# interface.net
KiCad netlist of a schematic drawn in Altium Designer
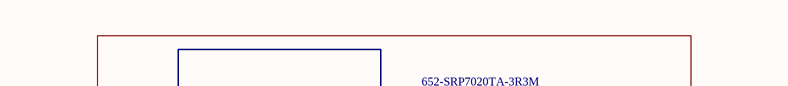
[diagram p0: interface.SchDoc, top left]
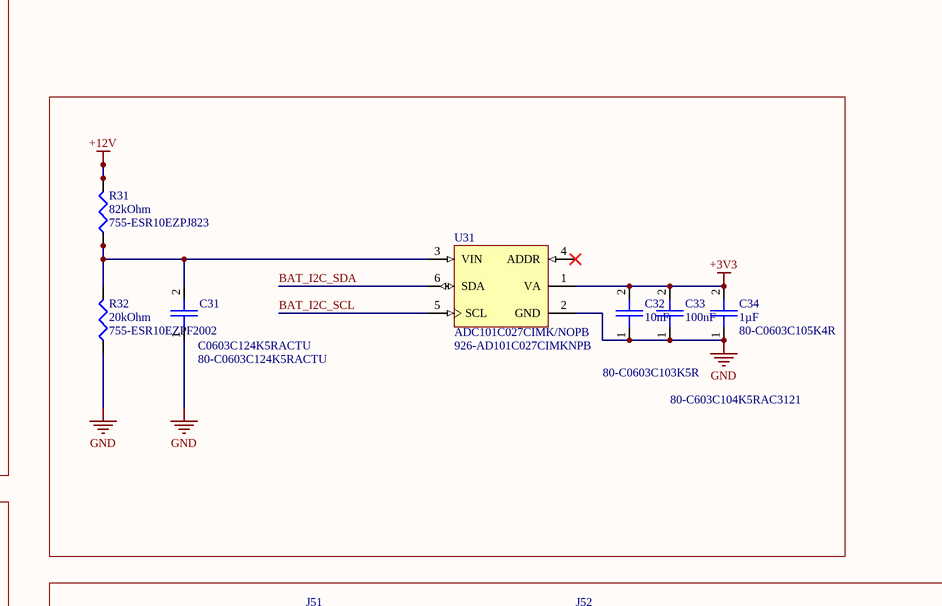
[diagram p1: interface.SchDoc, top right]
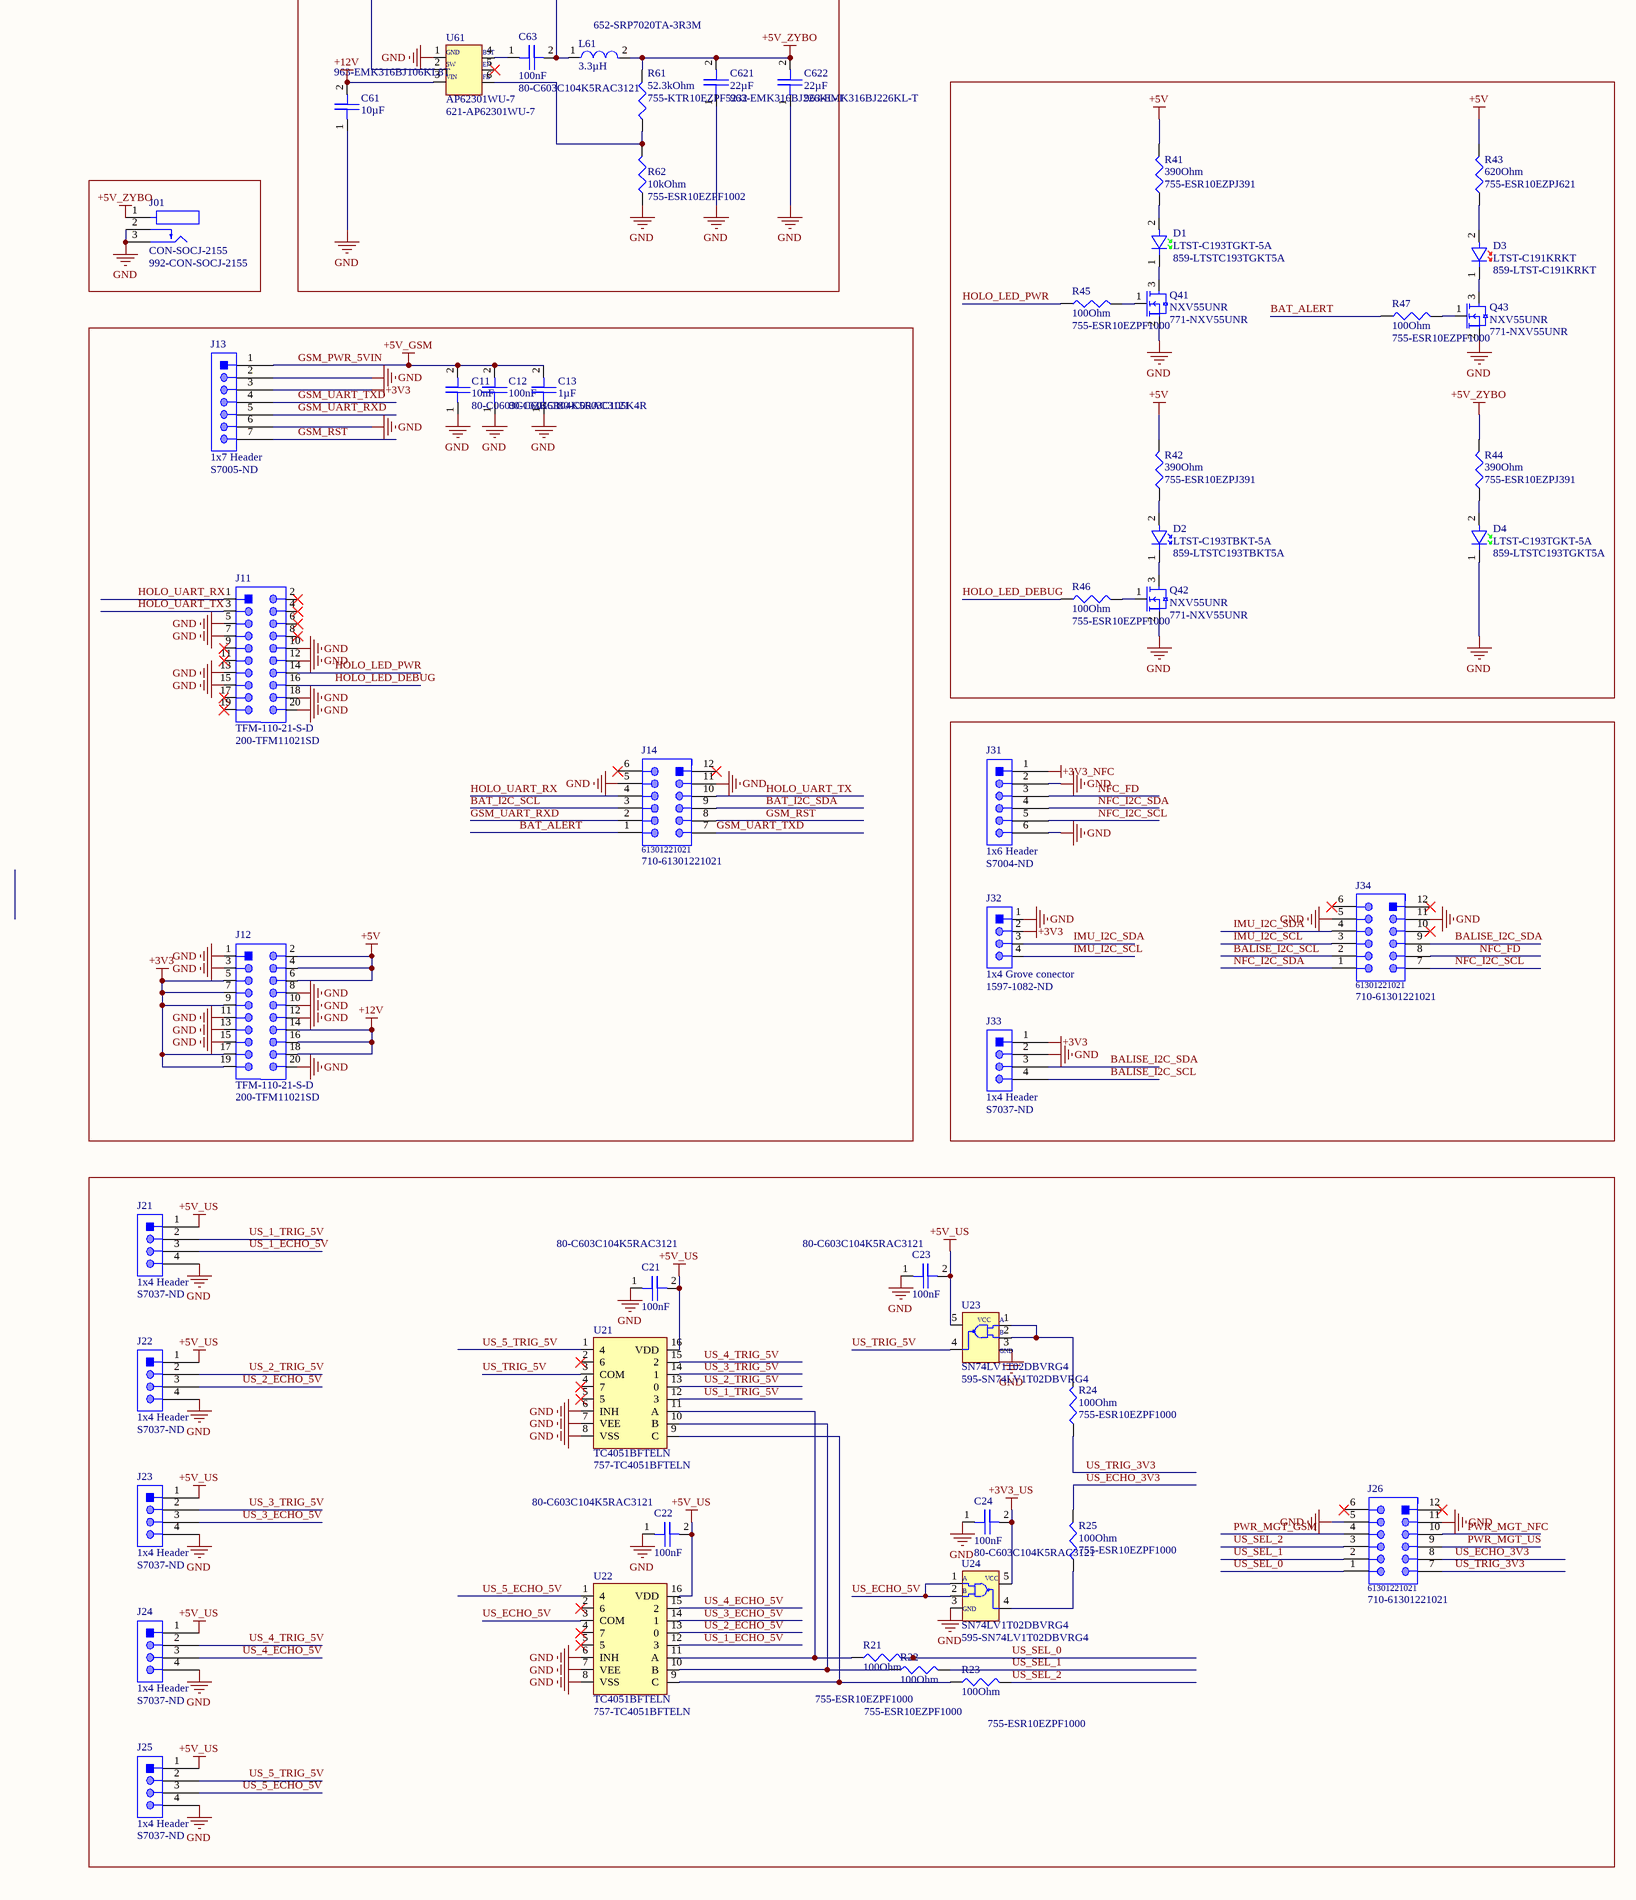
[diagram p2: interface.SchDoc, bottom left]
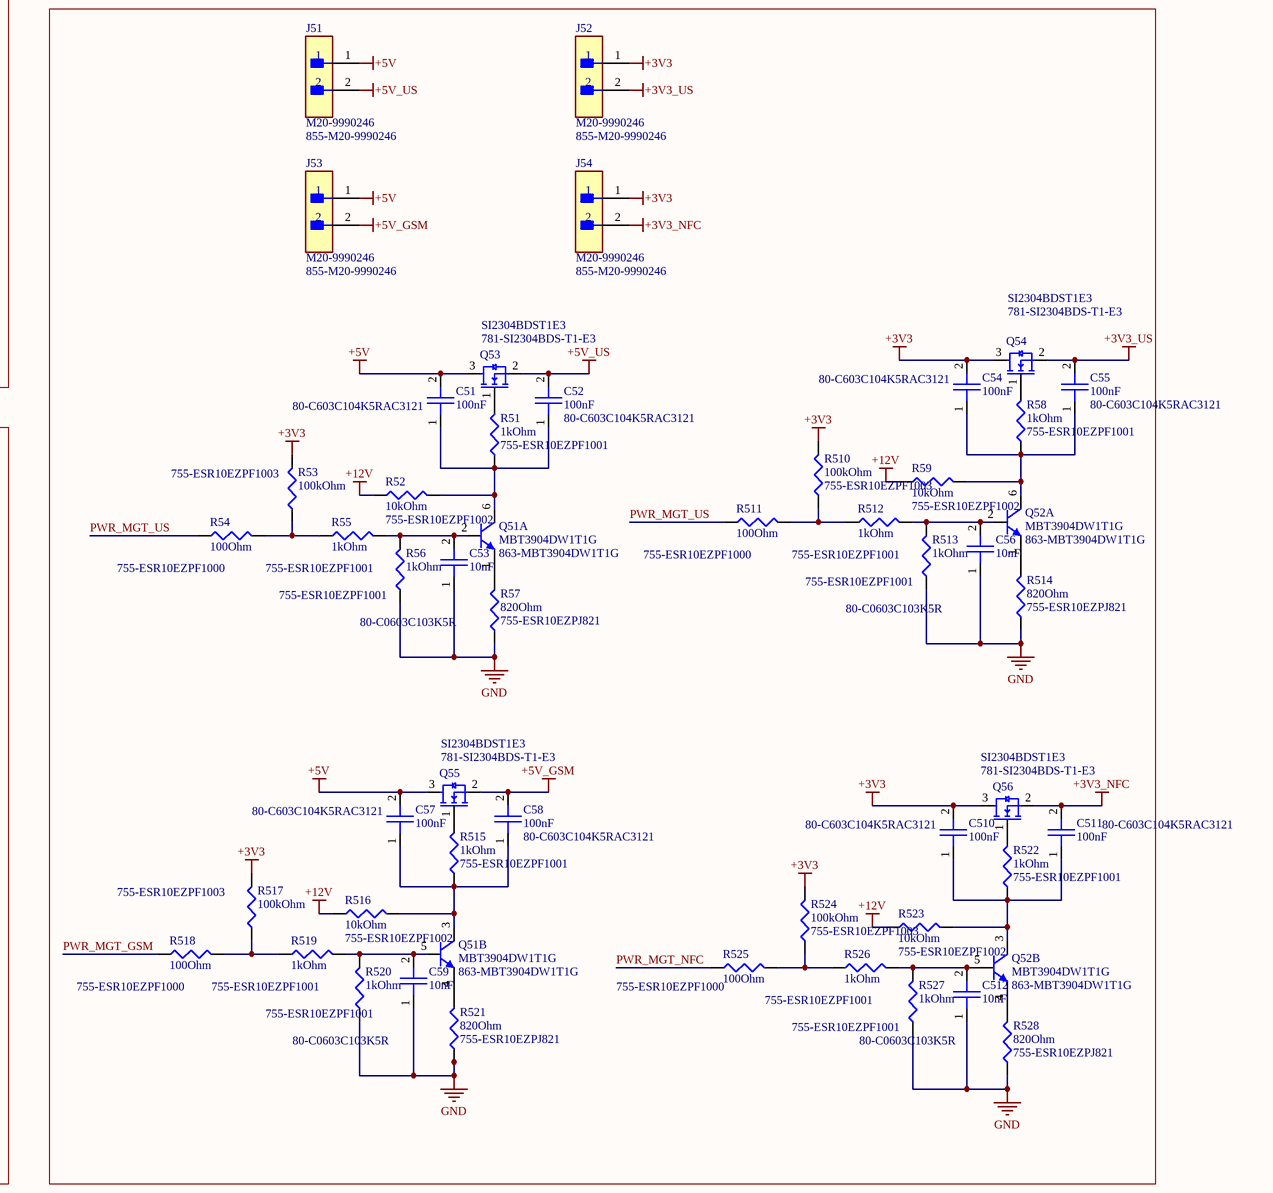
[diagram p3: interface.SchDoc, bottom right]

(export (version "E")
  (design (tool "Eeschema 10.0.6"))
  (components
    (comp (ref "C11")
      (value "10nF")
      (footprint "FP-C0603C-CF-IPC_A")
      (description "CAP CER 10000PF 50V X7R 0603")
      (fields
        (field (name "MANUFACTURER") "KEMET")
        (field (name "MANUFACTURER PART NUMBER") "C0603C103K5RACTU")
        (field (name "SUPPLIER PART NUMBER 1") "80-C0603C103K5R")
      )
      (libsource (lib "interface_Schlib") (part "C0603C103K5RACTU"))
    )
    (comp (ref "C12")
      (value "100nF")
      (footprint "FP-C0603C104K5RAC3121-IPC_A")
      (description "Cap Ceramic 0.1uF 50V X7R 10% Pad SMD 0603 125°C T/R")
      (fields
        (field (name "MANUFACTURER") "KEMET")
        (field (name "MANUFACTURER PART NUMBER") "C0603C104K5RAC3121")
        (field (name "SUPPLIER PART NUMBER 1") "80-C603C104K5RAC3121")
      )
      (libsource (lib "interface_Schlib") (part "C0603C104K5RAC3121"))
    )
    (comp (ref "C13")
      (value "1µF")
      (footprint "CAPC1608X90X35NL15T15")
      (description "Cap Ceramic 1uF 16V X7R 10% SMD 0603 125°C Paper T/R")
      (fields
        (field (name "MANUFACTURER") "KEMET")
        (field (name "MANUFACTURER PART NUMBER") "C0603C105K4RACTU")
        (field (name "SUPPLIER PART NUMBER 1") "80-C0603C105K4R")
      )
      (libsource (lib "interface_Schlib") (part "C0603C105K4RACTU"))
    )
    (comp (ref "C21")
      (value "100nF")
      (footprint "FP-C0603C104K5RAC3121-IPC_A")
      (description "Cap Ceramic 0.1uF 50V X7R 10% Pad SMD 0603 125°C T/R")
      (fields
        (field (name "MANUFACTURER") "KEMET")
        (field (name "MANUFACTURER PART NUMBER") "C0603C104K5RAC3121")
        (field (name "SUPPLIER PART NUMBER 1") "80-C603C104K5RAC3121")
      )
      (libsource (lib "interface_Schlib") (part "C0603C104K5RAC3121"))
    )
    (comp (ref "C22")
      (value "100nF")
      (footprint "FP-C0603C104K5RAC3121-IPC_A")
      (description "Cap Ceramic 0.1uF 50V X7R 10% Pad SMD 0603 125°C T/R")
      (fields
        (field (name "MANUFACTURER") "KEMET")
        (field (name "MANUFACTURER PART NUMBER") "C0603C104K5RAC3121")
        (field (name "SUPPLIER PART NUMBER 1") "80-C603C104K5RAC3121")
      )
      (libsource (lib "interface_Schlib") (part "C0603C104K5RAC3121"))
    )
    (comp (ref "C23")
      (value "100nF")
      (footprint "FP-C0603C104K5RAC3121-IPC_A")
      (description "Cap Ceramic 0.1uF 50V X7R 10% Pad SMD 0603 125°C T/R")
      (fields
        (field (name "MANUFACTURER") "KEMET")
        (field (name "MANUFACTURER PART NUMBER") "C0603C104K5RAC3121")
        (field (name "SUPPLIER PART NUMBER 1") "80-C603C104K5RAC3121")
      )
      (libsource (lib "interface_Schlib") (part "C0603C104K5RAC3121"))
    )
    (comp (ref "C24")
      (value "100nF")
      (footprint "FP-C0603C104K5RAC3121-IPC_A")
      (description "Cap Ceramic 0.1uF 50V X7R 10% Pad SMD 0603 125°C T/R")
      (fields
        (field (name "MANUFACTURER") "KEMET")
        (field (name "MANUFACTURER PART NUMBER") "C0603C104K5RAC3121")
        (field (name "SUPPLIER PART NUMBER 1") "80-C603C104K5RAC3121")
      )
      (libsource (lib "interface_Schlib") (part "C0603C104K5RAC3121"))
    )
    (comp (ref "C31")
      (value "C0603C124K5RACTU")
      (footprint "FP-C0603C-CF-IPC_A")
      (description "0603 C 120nF Ceramic Multilayer Capacitor; 50 V; +125degC; X7R Dielec; +/-10%")
      (fields
        (field (name "MANUFACTURER") "KEMET")
        (field (name "TOLERANCE") "10%")
        (field (name "SUPPLIER PART NUMBER 1") "80-C0603C124K5RACTU")
      )
      (libsource (lib "interface_Schlib") (part "C0603C124K5RACTU"))
    )
    (comp (ref "C32")
      (value "10nF")
      (footprint "FP-C0603C-CF-IPC_A")
      (description "CAP CER 10000PF 50V X7R 0603")
      (fields
        (field (name "MANUFACTURER") "KEMET")
        (field (name "MANUFACTURER PART NUMBER") "C0603C103K5RACTU")
        (field (name "SUPPLIER PART NUMBER 1") "80-C0603C103K5R")
      )
      (libsource (lib "interface_Schlib") (part "C0603C103K5RACTU"))
    )
    (comp (ref "C33")
      (value "100nF")
      (footprint "FP-C0603C104K5RAC3121-IPC_A")
      (description "Cap Ceramic 0.1uF 50V X7R 10% Pad SMD 0603 125°C T/R")
      (fields
        (field (name "MANUFACTURER") "KEMET")
        (field (name "MANUFACTURER PART NUMBER") "C0603C104K5RAC3121")
        (field (name "SUPPLIER PART NUMBER 1") "80-C603C104K5RAC3121")
      )
      (libsource (lib "interface_Schlib") (part "C0603C104K5RAC3121"))
    )
    (comp (ref "C34")
      (value "1µF")
      (footprint "CAPC1608X90X35NL15T15")
      (description "Cap Ceramic 1uF 16V X7R 10% SMD 0603 125°C Paper T/R")
      (fields
        (field (name "MANUFACTURER") "KEMET")
        (field (name "MANUFACTURER PART NUMBER") "C0603C105K4RACTU")
        (field (name "SUPPLIER PART NUMBER 1") "80-C0603C105K4R")
      )
      (libsource (lib "interface_Schlib") (part "C0603C105K4RACTU"))
    )
    (comp (ref "C51")
      (value "100nF")
      (footprint "FP-C0603C104K5RAC3121-IPC_A")
      (description "Cap Ceramic 0.1uF 50V X7R 10% Pad SMD 0603 125°C T/R")
      (fields
        (field (name "MANUFACTURER") "KEMET")
        (field (name "MANUFACTURER PART NUMBER") "C0603C104K5RAC3121")
        (field (name "SUPPLIER PART NUMBER 1") "80-C603C104K5RAC3121")
      )
      (libsource (lib "interface_Schlib") (part "C0603C104K5RAC3121"))
    )
    (comp (ref "C52")
      (value "100nF")
      (footprint "FP-C0603C104K5RAC3121-IPC_A")
      (description "Cap Ceramic 0.1uF 50V X7R 10% Pad SMD 0603 125°C T/R")
      (fields
        (field (name "MANUFACTURER") "KEMET")
        (field (name "MANUFACTURER PART NUMBER") "C0603C104K5RAC3121")
        (field (name "SUPPLIER PART NUMBER 1") "80-C603C104K5RAC3121")
      )
      (libsource (lib "interface_Schlib") (part "C0603C104K5RAC3121"))
    )
    (comp (ref "C53")
      (value "10nF")
      (footprint "FP-C0603C-CF-IPC_A")
      (description "CAP CER 10000PF 50V X7R 0603")
      (fields
        (field (name "MANUFACTURER") "KEMET")
        (field (name "MANUFACTURER PART NUMBER") "C0603C103K5RACTU")
        (field (name "SUPPLIER PART NUMBER 1") "80-C0603C103K5R")
      )
      (libsource (lib "interface_Schlib") (part "C0603C103K5RACTU"))
    )
    (comp (ref "C54")
      (value "100nF")
      (footprint "FP-C0603C104K5RAC3121-IPC_A")
      (description "Cap Ceramic 0.1uF 50V X7R 10% Pad SMD 0603 125°C T/R")
      (fields
        (field (name "MANUFACTURER") "KEMET")
        (field (name "MANUFACTURER PART NUMBER") "C0603C104K5RAC3121")
        (field (name "SUPPLIER PART NUMBER 1") "80-C603C104K5RAC3121")
      )
      (libsource (lib "interface_Schlib") (part "C0603C104K5RAC3121"))
    )
    (comp (ref "C55")
      (value "100nF")
      (footprint "FP-C0603C104K5RAC3121-IPC_A")
      (description "Cap Ceramic 0.1uF 50V X7R 10% Pad SMD 0603 125°C T/R")
      (fields
        (field (name "MANUFACTURER") "KEMET")
        (field (name "MANUFACTURER PART NUMBER") "C0603C104K5RAC3121")
        (field (name "SUPPLIER PART NUMBER 1") "80-C603C104K5RAC3121")
      )
      (libsource (lib "interface_Schlib") (part "C0603C104K5RAC3121"))
    )
    (comp (ref "C56")
      (value "10nF")
      (footprint "FP-C0603C-CF-IPC_A")
      (description "CAP CER 10000PF 50V X7R 0603")
      (fields
        (field (name "MANUFACTURER") "KEMET")
        (field (name "MANUFACTURER PART NUMBER") "C0603C103K5RACTU")
        (field (name "SUPPLIER PART NUMBER 1") "80-C0603C103K5R")
      )
      (libsource (lib "interface_Schlib") (part "C0603C103K5RACTU"))
    )
    (comp (ref "C57")
      (value "100nF")
      (footprint "FP-C0603C104K5RAC3121-IPC_A")
      (description "Cap Ceramic 0.1uF 50V X7R 10% Pad SMD 0603 125°C T/R")
      (fields
        (field (name "MANUFACTURER") "KEMET")
        (field (name "MANUFACTURER PART NUMBER") "C0603C104K5RAC3121")
        (field (name "SUPPLIER PART NUMBER 1") "80-C603C104K5RAC3121")
      )
      (libsource (lib "interface_Schlib") (part "C0603C104K5RAC3121"))
    )
    (comp (ref "C58")
      (value "100nF")
      (footprint "FP-C0603C104K5RAC3121-IPC_A")
      (description "Cap Ceramic 0.1uF 50V X7R 10% Pad SMD 0603 125°C T/R")
      (fields
        (field (name "MANUFACTURER") "KEMET")
        (field (name "MANUFACTURER PART NUMBER") "C0603C104K5RAC3121")
        (field (name "SUPPLIER PART NUMBER 1") "80-C603C104K5RAC3121")
      )
      (libsource (lib "interface_Schlib") (part "C0603C104K5RAC3121"))
    )
    (comp (ref "C59")
      (value "10nF")
      (footprint "FP-C0603C-CF-IPC_A")
      (description "CAP CER 10000PF 50V X7R 0603")
      (fields
        (field (name "MANUFACTURER") "KEMET")
        (field (name "MANUFACTURER PART NUMBER") "C0603C103K5RACTU")
        (field (name "SUPPLIER PART NUMBER 1") "80-C0603C103K5R")
      )
      (libsource (lib "interface_Schlib") (part "C0603C103K5RACTU"))
    )
    (comp (ref "C61")
      (value "10µF")
      (footprint "FP-1206-L_3_2_0_15-W_1_6-IPC_A")
      (description "Capacitor Ceramic 10uF 16V X5R 10% SMD 1206 85°C Embossed T/R")
      (fields
        (field (name "MANUFACTURER") "Taiyo Yuden")
        (field (name "MANUFACTURER PART NUMBER") "EMK316BJ106KL8T")
        (field (name "SUPPLIER PART NUMBER 1") "963-EMK316BJ106KL8T")
      )
      (libsource (lib "interface_Schlib") (part "EMK316BJ106KL8T"))
    )
    (comp (ref "C63")
      (value "100nF")
      (footprint "FP-C0603C104K5RAC3121-IPC_A")
      (description "Cap Ceramic 0.1uF 50V X7R 10% Pad SMD 0603 125°C T/R")
      (fields
        (field (name "MANUFACTURER") "KEMET")
        (field (name "MANUFACTURER PART NUMBER") "C0603C104K5RAC3121")
        (field (name "SUPPLIER PART NUMBER 1") "80-C603C104K5RAC3121")
      )
      (libsource (lib "interface_Schlib") (part "C0603C104K5RAC3121"))
    )
    (comp (ref "C510")
      (value "100nF")
      (footprint "FP-C0603C104K5RAC3121-IPC_A")
      (description "Cap Ceramic 0.1uF 50V X7R 10% Pad SMD 0603 125°C T/R")
      (fields
        (field (name "MANUFACTURER") "KEMET")
        (field (name "MANUFACTURER PART NUMBER") "C0603C104K5RAC3121")
        (field (name "SUPPLIER PART NUMBER 1") "80-C603C104K5RAC3121")
      )
      (libsource (lib "interface_Schlib") (part "C0603C104K5RAC3121"))
    )
    (comp (ref "C511")
      (value "100nF")
      (footprint "FP-C0603C104K5RAC3121-IPC_A")
      (description "Cap Ceramic 0.1uF 50V X7R 10% Pad SMD 0603 125°C T/R")
      (fields
        (field (name "MANUFACTURER") "KEMET")
        (field (name "MANUFACTURER PART NUMBER") "C0603C104K5RAC3121")
        (field (name "SUPPLIER PART NUMBER 1") "80-C603C104K5RAC3121")
      )
      (libsource (lib "interface_Schlib") (part "C0603C104K5RAC3121"))
    )
    (comp (ref "C512")
      (value "10nF")
      (footprint "FP-C0603C-CF-IPC_A")
      (description "CAP CER 10000PF 50V X7R 0603")
      (fields
        (field (name "MANUFACTURER") "KEMET")
        (field (name "MANUFACTURER PART NUMBER") "C0603C103K5RACTU")
        (field (name "SUPPLIER PART NUMBER 1") "80-C0603C103K5R")
      )
      (libsource (lib "interface_Schlib") (part "C0603C103K5RACTU"))
    )
    (comp (ref "C621")
      (value "22µF")
      (footprint "CAPC3216X180N")
      (description "Cap Ceramic 22uF 16V X7R 10% SMD 0805 125°C Paper T/R")
      (fields
        (field (name "MANUFACTURER") "Taiyo Yuden")
        (field (name "MANUFACTURER PART NUMBER") "EMK316BJ226KL-T")
        (field (name "SUPPLIER PART NUMBER 1") "963-EMK316BJ226KL-T")
      )
      (libsource (lib "station_de_charge_SchLib") (part "EMK316BJ226KL-T"))
    )
    (comp (ref "C622")
      (value "22µF")
      (footprint "CAPC3216X180N")
      (description "Cap Ceramic 22uF 16V X7R 10% SMD 0805 125°C Paper T/R")
      (fields
        (field (name "MANUFACTURER") "Taiyo Yuden")
        (field (name "MANUFACTURER PART NUMBER") "EMK316BJ226KL-T")
        (field (name "SUPPLIER PART NUMBER 1") "963-EMK316BJ226KL-T")
      )
      (libsource (lib "station_de_charge_SchLib") (part "EMK316BJ226KL-T"))
    )
    (comp (ref "D1")
      (value "LTST-C193TGKT-5A")
      (footprint "FP-LTST-C193TGKT-5A")
      (description "0603(H=0.35mm) 绿色 λD=520nm~535nm VR=5V VF=2.5V~3.1V IF=5mA PD=76mW")
      (fields
        (field (name "MANUFACTURER") "Vishay Lite-On")
        (field (name "SUPPLIER PART NUMBER 1") "859-LTSTC193TGKT5A")
      )
      (libsource (lib "interface_Schlib") (part "LTST-C193TGKT-5A"))
    )
    (comp (ref "D2")
      (value "LTST-C193TBKT-5A")
      (footprint "FP-LTST-C193TBKT-5A-MFG")
      (description "0603(H=0.35mm) 蓝色 λD=465nm~475nm VR=5V VF=2.65V~3.05V IF=5mA PD=76mW")
      (fields
        (field (name "MANUFACTURER") "Vishay Lite-On")
        (field (name "SUPPLIER PART NUMBER 1") "859-LTSTC193TBKT5A")
      )
      (libsource (lib "interface_Schlib") (part "LTST-C193TBKT-5A"))
    )
    (comp (ref "D3")
      (value "LTST-C191KRKT")
      (footprint "FP-LTST-C191KRKT")
      (description "0603(H=0.65mm) 红色 λD=631nm VR=5V VF=2.0V~2.4V IF=20mA PD=75mW")
      (fields
        (field (name "MANUFACTURER") "Vishay Lite-On")
        (field (name "SUPPLIER PART NUMBER 1") "859-LTST-C191KRKT")
        (field (name "VOLTAGE") "2V")
      )
      (libsource (lib "interface_Schlib") (part "LTST-C191KRKT"))
    )
    (comp (ref "D4")
      (value "LTST-C193TGKT-5A")
      (footprint "FP-LTST-C193TGKT-5A")
      (description "0603(H=0.35mm) 绿色 λD=520nm~535nm VR=5V VF=2.5V~3.1V IF=5mA PD=76mW")
      (fields
        (field (name "MANUFACTURER") "Vishay Lite-On")
        (field (name "SUPPLIER PART NUMBER 1") "859-LTSTC193TGKT5A")
      )
      (libsource (lib "interface_Schlib") (part "LTST-C193TGKT-5A"))
    )
    (comp (ref "J01")
      (value "CON-SOCJ-2155")
      (footprint "GRAVITECH_CON-SOCJ-2155")
      (description "DC Power Connectors Power Jack/Connector 2.1mm x 5.5mm")
      (fields
        (field (name "MANUFACTURER") "Gravitech")
        (field (name "SUPPLIER PART NUMBER 1") "992-CON-SOCJ-2155")
      )
      (libsource (lib "interface_Schlib") (part "CON-SOCJ-2155"))
    )
    (comp (ref "J11")
      (value "TFM-110-21-S-D")
      (footprint "SAMTEC_TFM-110-21-S-D")
      (fields (field (name "MANUFACTURER") "Samtec") (field (name "SUPPLIER PART NUMBER 1") "200-TFM11021SD"))
      (libsource (lib "interface_Schlib") (part "TFM-110-21-S-D"))
    )
    (comp (ref "J12")
      (value "TFM-110-21-S-D")
      (footprint "SAMTEC_TFM-110-21-S-D")
      (fields (field (name "MANUFACTURER") "Samtec") (field (name "SUPPLIER PART NUMBER 1") "200-TFM11021SD"))
      (libsource (lib "interface_Schlib") (part "TFM-110-21-S-D"))
    )
    (comp (ref "J13")
      (value "1x7 Header")
      (footprint "header 1x7")
      (description "Female, 7C, Straight, .100\"CC; 3.20mm Tail, No Mt. 100u\" Tin; PBT, Phos Bronze, 105 C")
      (fields
        (field (name "MANUFACTURER") "Sullins")
        (field (name "MANUFACTURER PART NUMBER") "PPTC071LFBN-RC")
        (field (name "SUPPLIER PART NUMBER 1") "S7005-ND")
      )
      (libsource (lib "interface_Schlib") (part "PPTC071LFBN-RC"))
    )
    (comp (ref "J14")
      (value "61301221021")
      (footprint "61301221021")
      (description "THT Angled Pin Header WR-PHD, Pitch 2.54 mm, Dual Row, 12 pins")
      (fields
        (field (name "MANUFACTURER") "Wurth Elektronik")
        (field (name "SUPPLIER PART NUMBER 1") "710-61301221021")
        (field (name "PUBLISHER") "WurthElektronik")
      )
      (libsource (lib "interface_Schlib") (part "61301221021"))
    )
    (comp (ref "J21")
      (value "1x4 Header")
      (footprint "header 1x4")
      (description "4 Positions Embase Connecteur 0,100 po (2,54mm) Trou traversant Or")
      (fields
        (field (name "MANUFACTURER") "Sullins")
        (field (name "MANUFACTURER PART NUMBER") "PPPC041LFBN-RC")
        (field (name "SUPPLIER PART NUMBER 1") "S7037-ND")
      )
      (libsource (lib "interface_Schlib") (part "PPPC041LFBN-RC"))
    )
    (comp (ref "J22")
      (value "1x4 Header")
      (footprint "header 1x4")
      (description "4 Positions Embase Connecteur 0,100 po (2,54mm) Trou traversant Or")
      (fields
        (field (name "MANUFACTURER") "Sullins")
        (field (name "MANUFACTURER PART NUMBER") "PPPC041LFBN-RC")
        (field (name "SUPPLIER PART NUMBER 1") "S7037-ND")
      )
      (libsource (lib "interface_Schlib") (part "PPPC041LFBN-RC"))
    )
    (comp (ref "J23")
      (value "1x4 Header")
      (footprint "header 1x4")
      (description "4 Positions Embase Connecteur 0,100 po (2,54mm) Trou traversant Or")
      (fields
        (field (name "MANUFACTURER") "Sullins")
        (field (name "MANUFACTURER PART NUMBER") "PPPC041LFBN-RC")
        (field (name "SUPPLIER PART NUMBER 1") "S7037-ND")
      )
      (libsource (lib "interface_Schlib") (part "PPPC041LFBN-RC"))
    )
    (comp (ref "J24")
      (value "1x4 Header")
      (footprint "header 1x4")
      (description "4 Positions Embase Connecteur 0,100 po (2,54mm) Trou traversant Or")
      (fields
        (field (name "MANUFACTURER") "Sullins")
        (field (name "MANUFACTURER PART NUMBER") "PPPC041LFBN-RC")
        (field (name "SUPPLIER PART NUMBER 1") "S7037-ND")
      )
      (libsource (lib "interface_Schlib") (part "PPPC041LFBN-RC"))
    )
    (comp (ref "J25")
      (value "1x4 Header")
      (footprint "header 1x4")
      (description "4 Positions Embase Connecteur 0,100 po (2,54mm) Trou traversant Or")
      (fields
        (field (name "MANUFACTURER") "Sullins")
        (field (name "MANUFACTURER PART NUMBER") "PPPC041LFBN-RC")
        (field (name "SUPPLIER PART NUMBER 1") "S7037-ND")
      )
      (libsource (lib "interface_Schlib") (part "PPPC041LFBN-RC"))
    )
    (comp (ref "J26")
      (value "61301221021")
      (footprint "61301221021")
      (description "THT Angled Pin Header WR-PHD, Pitch 2.54 mm, Dual Row, 12 pins")
      (fields
        (field (name "MANUFACTURER") "Wurth Elektronik")
        (field (name "SUPPLIER PART NUMBER 1") "710-61301221021")
        (field (name "PUBLISHER") "WurthElektronik")
      )
      (libsource (lib "interface_Schlib") (part "61301221021"))
    )
    (comp (ref "J31")
      (value "1x6 Header")
      (footprint "header 1x6")
      (description "Female, 6 C, Straight, .100\"CC; 3.20mm Tail, No Mt. 100u\" Tin; PBT, Phos Bronze, 105 C")
      (fields
        (field (name "MANUFACTURER") "Sullins")
        (field (name "MANUFACTURER PART NUMBER") "PPTC061LFBN-RC")
        (field (name "SUPPLIER PART NUMBER 1") "S7004-ND")
      )
      (libsource (lib "interface_Schlib") (part "PPTC061LFBN-RC"))
    )
    (comp (ref "J32")
      (value "1x4 Grove conector")
      (footprint "FP-110990030")
      (description "Grove - Universal 4 pin connector [Seeed Studio] 110990030 Grove - Universal 4 pin connector")
      (fields
        (field (name "MANUFACTURER") "Seeed Studio")
        (field (name "MANUFACTURER PART NUMBER") "110990030")
        (field (name "SUPPLIER PART NUMBER 1") "1597-1082-ND")
      )
      (libsource (lib "interface_Schlib") (part "110990030"))
    )
    (comp (ref "J33")
      (value "1x4 Header")
      (footprint "header 1x4")
      (description "4 Positions Embase Connecteur 0,100 po (2,54mm) Trou traversant Or")
      (fields
        (field (name "MANUFACTURER") "Sullins")
        (field (name "MANUFACTURER PART NUMBER") "PPPC041LFBN-RC")
        (field (name "SUPPLIER PART NUMBER 1") "S7037-ND")
      )
      (libsource (lib "interface_Schlib") (part "PPPC041LFBN-RC"))
    )
    (comp (ref "J34")
      (value "61301221021")
      (footprint "61301221021")
      (description "THT Angled Pin Header WR-PHD, Pitch 2.54 mm, Dual Row, 12 pins")
      (fields
        (field (name "MANUFACTURER") "Wurth Elektronik")
        (field (name "SUPPLIER PART NUMBER 1") "710-61301221021")
        (field (name "PUBLISHER") "WurthElektronik")
      )
      (libsource (lib "interface_Schlib") (part "61301221021"))
    )
    (comp (ref "J51")
      (value "M20-9990246")
      (footprint "FP-M20-9990246-MFG")
      (description "2.54mm (0.1\") Pitch SIL Vertical PC Tail Pin Header, 6.1mm mating pin height, tin, 2 contacts")
      (fields
        (field (name "MANUFACTURER") "Harwin")
        (field (name "SUPPLIER PART NUMBER 1") "855-M20-9990246")
      )
      (libsource (lib "interface_Schlib") (part "M20-9990246"))
    )
    (comp (ref "J52")
      (value "M20-9990246")
      (footprint "FP-M20-9990246-MFG")
      (description "2.54mm (0.1\") Pitch SIL Vertical PC Tail Pin Header, 6.1mm mating pin height, tin, 2 contacts")
      (fields
        (field (name "MANUFACTURER") "Harwin")
        (field (name "SUPPLIER PART NUMBER 1") "855-M20-9990246")
      )
      (libsource (lib "interface_Schlib") (part "M20-9990246"))
    )
    (comp (ref "J53")
      (value "M20-9990246")
      (footprint "FP-M20-9990246-MFG")
      (description "2.54mm (0.1\") Pitch SIL Vertical PC Tail Pin Header, 6.1mm mating pin height, tin, 2 contacts")
      (fields
        (field (name "MANUFACTURER") "Harwin")
        (field (name "SUPPLIER PART NUMBER 1") "855-M20-9990246")
      )
      (libsource (lib "interface_Schlib") (part "M20-9990246"))
    )
    (comp (ref "J54")
      (value "M20-9990246")
      (footprint "FP-M20-9990246-MFG")
      (description "2.54mm (0.1\") Pitch SIL Vertical PC Tail Pin Header, 6.1mm mating pin height, tin, 2 contacts")
      (fields
        (field (name "MANUFACTURER") "Harwin")
        (field (name "SUPPLIER PART NUMBER 1") "855-M20-9990246")
      )
      (libsource (lib "interface_Schlib") (part "M20-9990246"))
    )
    (comp (ref "L61")
      (value "3.3µH")
      (footprint "INDC7066X20N")
      (fields
        (field (name "MANUFACTURER") "Bourns")
        (field (name "MANUFACTURER PART NUMBER") "SRP7020TA-3R3M")
        (field (name "SUPPLIER PART NUMBER 1") "652-SRP7020TA-3R3M")
      )
      (libsource (lib "interface_Schlib") (part "SRP7020TA-3R3M"))
    )
    (comp (ref "Q41")
      (value "NXV55UNR")
      (footprint "SOT95P230X110-3N")
      (description "Transistor MOSFET N-Channel 30V 2.3A 3-Pin SOT-23")
      (fields (field (name "MANUFACTURER") "Nexperia") (field (name "SUPPLIER PART NUMBER 1") "771-NXV55UNR"))
      (libsource (lib "interface_Schlib") (part "NXV55UNR"))
    )
    (comp (ref "Q42")
      (value "NXV55UNR")
      (footprint "SOT95P230X110-3N")
      (description "Transistor MOSFET N-Channel 30V 2.3A 3-Pin SOT-23")
      (fields (field (name "MANUFACTURER") "Nexperia") (field (name "SUPPLIER PART NUMBER 1") "771-NXV55UNR"))
      (libsource (lib "interface_Schlib") (part "NXV55UNR"))
    )
    (comp (ref "Q43")
      (value "NXV55UNR")
      (footprint "SOT95P230X110-3N")
      (description "Transistor MOSFET N-Channel 30V 2.3A 3-Pin SOT-23")
      (fields (field (name "MANUFACTURER") "Nexperia") (field (name "SUPPLIER PART NUMBER 1") "771-NXV55UNR"))
      (libsource (lib "interface_Schlib") (part "NXV55UNR"))
    )
    (comp (ref "Q51")
      (value "MBT3904DW1T1G")
      (footprint "ONSC-SOT-363-6-419B-02_W_V")
      (description "Dual General Purpose Transistors, 6-Pin SOT-363, Pb-Free, Tape and Reel")
      (fields
        (field (name "MANUFACTURER") "On Semiconductor")
        (field (name "SUPPLIER PART NUMBER 1") "863-MBT3904DW1T1G")
      )
      (libsource (lib "interface_Schlib") (part "CMP-1048-00877-1"))
    )
    (comp (ref "Q52")
      (value "MBT3904DW1T1G")
      (footprint "ONSC-SOT-363-6-419B-02_W_V")
      (description "Dual General Purpose Transistors, 6-Pin SOT-363, Pb-Free, Tape and Reel")
      (fields
        (field (name "MANUFACTURER") "On Semiconductor")
        (field (name "SUPPLIER PART NUMBER 1") "863-MBT3904DW1T1G")
      )
      (libsource (lib "interface_Schlib") (part "CMP-1048-00877-1"))
    )
    (comp (ref "Q53")
      (value "SI2304BDST1E3")
      (footprint "FP-SI2304BDST1E3")
      (description "Single N-Channel 30 V 0.07 Ohms Surface Mount Power Mosfet - SOT-23")
      (fields
        (field (name "MANUFACTURER") "Vishay")
        (field (name "SUPPLIER PART NUMBER 1") "781-SI2304BDS-T1-E3")
      )
      (libsource (lib "interface_Schlib") (part "SI2304BDST1E3"))
    )
    (comp (ref "Q54")
      (value "SI2304BDST1E3")
      (footprint "FP-SI2304BDST1E3")
      (description "Single N-Channel 30 V 0.07 Ohms Surface Mount Power Mosfet - SOT-23")
      (fields
        (field (name "MANUFACTURER") "Vishay")
        (field (name "SUPPLIER PART NUMBER 1") "781-SI2304BDS-T1-E3")
      )
      (libsource (lib "interface_Schlib") (part "SI2304BDST1E3"))
    )
    (comp (ref "Q55")
      (value "SI2304BDST1E3")
      (footprint "FP-SI2304BDST1E3")
      (description "Single N-Channel 30 V 0.07 Ohms Surface Mount Power Mosfet - SOT-23")
      (fields
        (field (name "MANUFACTURER") "Vishay")
        (field (name "SUPPLIER PART NUMBER 1") "781-SI2304BDS-T1-E3")
      )
      (libsource (lib "interface_Schlib") (part "SI2304BDST1E3"))
    )
    (comp (ref "Q56")
      (value "SI2304BDST1E3")
      (footprint "FP-SI2304BDST1E3")
      (description "Single N-Channel 30 V 0.07 Ohms Surface Mount Power Mosfet - SOT-23")
      (fields
        (field (name "MANUFACTURER") "Vishay")
        (field (name "SUPPLIER PART NUMBER 1") "781-SI2304BDS-T1-E3")
      )
      (libsource (lib "interface_Schlib") (part "SI2304BDST1E3"))
    )
    (comp (ref "R21")
      (value "100Ohm")
      (footprint "FP-ESR10-IPC_A")
      (description "Res Thick Film 0805 100 Ohm 1% 2/5W ±100ppm/°C Molded SMD Paper T/R")
      (fields
        (field (name "MANUFACTURER") "Rohm")
        (field (name "MANUFACTURER PART NUMBER") "ESR10EZPF1000")
        (field (name "SUPPLIER PART NUMBER 1") "755-ESR10EZPF1000")
      )
      (libsource (lib "interface_Schlib") (part "ESR10EZPF1000"))
    )
    (comp (ref "R22")
      (value "100Ohm")
      (footprint "FP-ESR10-IPC_A")
      (description "Res Thick Film 0805 100 Ohm 1% 2/5W ±100ppm/°C Molded SMD Paper T/R")
      (fields
        (field (name "MANUFACTURER") "Rohm")
        (field (name "MANUFACTURER PART NUMBER") "ESR10EZPF1000")
        (field (name "SUPPLIER PART NUMBER 1") "755-ESR10EZPF1000")
      )
      (libsource (lib "interface_Schlib") (part "ESR10EZPF1000"))
    )
    (comp (ref "R23")
      (value "100Ohm")
      (footprint "FP-ESR10-IPC_A")
      (description "Res Thick Film 0805 100 Ohm 1% 2/5W ±100ppm/°C Molded SMD Paper T/R")
      (fields
        (field (name "MANUFACTURER") "Rohm")
        (field (name "MANUFACTURER PART NUMBER") "ESR10EZPF1000")
        (field (name "SUPPLIER PART NUMBER 1") "755-ESR10EZPF1000")
      )
      (libsource (lib "interface_Schlib") (part "ESR10EZPF1000"))
    )
    (comp (ref "R24")
      (value "100Ohm")
      (footprint "FP-ESR10-IPC_A")
      (description "Res Thick Film 0805 100 Ohm 1% 2/5W ±100ppm/°C Molded SMD Paper T/R")
      (fields
        (field (name "MANUFACTURER") "Rohm")
        (field (name "MANUFACTURER PART NUMBER") "ESR10EZPF1000")
        (field (name "SUPPLIER PART NUMBER 1") "755-ESR10EZPF1000")
      )
      (libsource (lib "interface_Schlib") (part "ESR10EZPF1000"))
    )
    (comp (ref "R25")
      (value "100Ohm")
      (footprint "FP-ESR10-IPC_A")
      (description "Res Thick Film 0805 100 Ohm 1% 2/5W ±100ppm/°C Molded SMD Paper T/R")
      (fields
        (field (name "MANUFACTURER") "Rohm")
        (field (name "MANUFACTURER PART NUMBER") "ESR10EZPF1000")
        (field (name "SUPPLIER PART NUMBER 1") "755-ESR10EZPF1000")
      )
      (libsource (lib "interface_Schlib") (part "ESR10EZPF1000"))
    )
    (comp (ref "R31")
      (value "82kOhm")
      (footprint "FP-ESR10-IPC_A")
      (description "Res Anti-surge 0805 82K Ohm 0.4W 5% SMD")
      (fields
        (field (name "MANUFACTURER") "Rohm")
        (field (name "MANUFACTURER PART NUMBER") "ESR10EZPJ823")
        (field (name "SUPPLIER PART NUMBER 1") "755-ESR10EZPJ823")
      )
      (libsource (lib "interface_Schlib") (part "ESR10EZPJ823"))
    )
    (comp (ref "R32")
      (value "20kOhm")
      (footprint "FP-ESR10-IPC_A")
      (description "Res Thick Film 0805 20KOhm 1% 2/5W ±100ppm/°C Molded SMD Paper T/R")
      (fields
        (field (name "MANUFACTURER") "Rohm")
        (field (name "MANUFACTURER PART NUMBER") "ESR10EZPF2002")
        (field (name "SUPPLIER PART NUMBER 1") "755-ESR10EZPF2002")
      )
      (libsource (lib "interface_Schlib") (part "ESR10EZPF2002"))
    )
    (comp (ref "R41")
      (value "390Ohm")
      (footprint "FP-ESR10-IPC_A")
      (description "Res Thick Film 0805 390 Ohm 5% 0.4W ±200ppm/C Pad SMD Automotive T/R")
      (fields
        (field (name "MANUFACTURER") "Rohm")
        (field (name "MANUFACTURER PART NUMBER") "ESR10EZPJ391")
        (field (name "SUPPLIER PART NUMBER 1") "755-ESR10EZPJ391")
      )
      (libsource (lib "interface_Schlib") (part "ESR10EZPJ391"))
    )
    (comp (ref "R42")
      (value "390Ohm")
      (footprint "FP-ESR10-IPC_A")
      (description "Res Thick Film 0805 390 Ohm 5% 0.4W ±200ppm/C Pad SMD Automotive T/R")
      (fields
        (field (name "MANUFACTURER") "Rohm")
        (field (name "MANUFACTURER PART NUMBER") "ESR10EZPJ391")
        (field (name "SUPPLIER PART NUMBER 1") "755-ESR10EZPJ391")
      )
      (libsource (lib "interface_Schlib") (part "ESR10EZPJ391"))
    )
    (comp (ref "R43")
      (value "620Ohm")
      (footprint "FP-ESR10-IPC_A")
      (description "Res Thick Film 0805 620 Ohm 5% 0.4W ±200ppm/C Pad SMD Automotive T/R")
      (fields
        (field (name "MANUFACTURER") "Rohm")
        (field (name "MANUFACTURER PART NUMBER") "ESR10EZPJ621")
        (field (name "SUPPLIER PART NUMBER 1") "755-ESR10EZPJ621")
      )
      (libsource (lib "interface_Schlib") (part "ESR10EZPJ621"))
    )
    (comp (ref "R44")
      (value "390Ohm")
      (footprint "FP-ESR10-IPC_A")
      (description "Res Thick Film 0805 390 Ohm 5% 0.4W ±200ppm/C Pad SMD Automotive T/R")
      (fields
        (field (name "MANUFACTURER") "Rohm")
        (field (name "MANUFACTURER PART NUMBER") "ESR10EZPJ391")
        (field (name "SUPPLIER PART NUMBER 1") "755-ESR10EZPJ391")
      )
      (libsource (lib "interface_Schlib") (part "ESR10EZPJ391"))
    )
    (comp (ref "R45")
      (value "100Ohm")
      (footprint "FP-ESR10-IPC_A")
      (description "Res Thick Film 0805 100 Ohm 1% 2/5W ±100ppm/°C Molded SMD Paper T/R")
      (fields
        (field (name "MANUFACTURER") "Rohm")
        (field (name "MANUFACTURER PART NUMBER") "ESR10EZPF1000")
        (field (name "SUPPLIER PART NUMBER 1") "755-ESR10EZPF1000")
      )
      (libsource (lib "interface_Schlib") (part "ESR10EZPF1000"))
    )
    (comp (ref "R46")
      (value "100Ohm")
      (footprint "FP-ESR10-IPC_A")
      (description "Res Thick Film 0805 100 Ohm 1% 2/5W ±100ppm/°C Molded SMD Paper T/R")
      (fields
        (field (name "MANUFACTURER") "Rohm")
        (field (name "MANUFACTURER PART NUMBER") "ESR10EZPF1000")
        (field (name "SUPPLIER PART NUMBER 1") "755-ESR10EZPF1000")
      )
      (libsource (lib "interface_Schlib") (part "ESR10EZPF1000"))
    )
    (comp (ref "R47")
      (value "100Ohm")
      (footprint "FP-ESR10-IPC_A")
      (description "Res Thick Film 0805 100 Ohm 1% 2/5W ±100ppm/°C Molded SMD Paper T/R")
      (fields
        (field (name "MANUFACTURER") "Rohm")
        (field (name "MANUFACTURER PART NUMBER") "ESR10EZPF1000")
        (field (name "SUPPLIER PART NUMBER 1") "755-ESR10EZPF1000")
      )
      (libsource (lib "interface_Schlib") (part "ESR10EZPF1000"))
    )
    (comp (ref "R51")
      (value "1kOhm")
      (footprint "FP-ESR10-IPC_A")
      (description "Res Thick Film 0805 1K Ohm 1% 0.4W ±100ppm/C Epoxy Resin Pad SMD Automotive T/R")
      (fields
        (field (name "MANUFACTURER") "Rohm")
        (field (name "MANUFACTURER PART NUMBER") "ESR10EZPF1001")
        (field (name "SUPPLIER PART NUMBER 1") "755-ESR10EZPF1001")
      )
      (libsource (lib "interface_Schlib") (part "ESR10EZPF1001"))
    )
    (comp (ref "R52")
      (value "10kOhm")
      (footprint "FP-ESR10-IPC_A")
      (description "Res Thick Film 0805 10K Ohm 1% 0.4W ±100ppm/C Pad SMD Automotive T/R")
      (fields
        (field (name "MANUFACTURER") "Rohm")
        (field (name "MANUFACTURER PART NUMBER") "ESR10EZPF1002")
        (field (name "SUPPLIER PART NUMBER 1") "755-ESR10EZPF1002")
      )
      (libsource (lib "interface_Schlib") (part "ESR10EZPF1002"))
    )
    (comp (ref "R53")
      (value "100kOhm")
      (footprint "FP-ESR10-IPC_A")
      (description "Res Thick Film 0805 100K Ohm 1% 0.4W ±100ppm/C Epoxy Resin Pad SMD Automotive T/R")
      (fields
        (field (name "MANUFACTURER") "Rohm")
        (field (name "MANUFACTURER PART NUMBER") "ESR10EZPF1003")
        (field (name "SUPPLIER PART NUMBER 1") "755-ESR10EZPF1003")
      )
      (libsource (lib "interface_Schlib") (part "ESR10EZPF1003"))
    )
    (comp (ref "R54")
      (value "100Ohm")
      (footprint "FP-ESR10-IPC_A")
      (description "Res Thick Film 0805 100 Ohm 1% 2/5W ±100ppm/°C Molded SMD Paper T/R")
      (fields
        (field (name "MANUFACTURER") "Rohm")
        (field (name "MANUFACTURER PART NUMBER") "ESR10EZPF1000")
        (field (name "SUPPLIER PART NUMBER 1") "755-ESR10EZPF1000")
      )
      (libsource (lib "interface_Schlib") (part "ESR10EZPF1000"))
    )
    (comp (ref "R55")
      (value "1kOhm")
      (footprint "FP-ESR10-IPC_A")
      (description "Res Thick Film 0805 1K Ohm 1% 0.4W ±100ppm/C Epoxy Resin Pad SMD Automotive T/R")
      (fields
        (field (name "MANUFACTURER") "Rohm")
        (field (name "MANUFACTURER PART NUMBER") "ESR10EZPF1001")
        (field (name "SUPPLIER PART NUMBER 1") "755-ESR10EZPF1001")
      )
      (libsource (lib "interface_Schlib") (part "ESR10EZPF1001"))
    )
    (comp (ref "R56")
      (value "1kOhm")
      (footprint "FP-ESR10-IPC_A")
      (description "Res Thick Film 0805 1K Ohm 1% 0.4W ±100ppm/C Epoxy Resin Pad SMD Automotive T/R")
      (fields
        (field (name "MANUFACTURER") "Rohm")
        (field (name "MANUFACTURER PART NUMBER") "ESR10EZPF1001")
        (field (name "SUPPLIER PART NUMBER 1") "755-ESR10EZPF1001")
      )
      (libsource (lib "interface_Schlib") (part "ESR10EZPF1001"))
    )
    (comp (ref "R57")
      (value "820Ohm")
      (footprint "FP-ESR10-IPC_A")
      (description "Res Thick Film 0805 820 Ohm 5% 0.4W ±200ppm/C Epoxy Resin Pad SMD Automotive T/R")
      (fields
        (field (name "MANUFACTURER") "Rohm")
        (field (name "MANUFACTURER PART NUMBER") "ESR10EZPJ821")
        (field (name "SUPPLIER PART NUMBER 1") "755-ESR10EZPJ821")
      )
      (libsource (lib "interface_Schlib") (part "ESR10EZPJ821"))
    )
    (comp (ref "R58")
      (value "1kOhm")
      (footprint "FP-ESR10-IPC_A")
      (description "Res Thick Film 0805 1K Ohm 1% 0.4W ±100ppm/C Epoxy Resin Pad SMD Automotive T/R")
      (fields
        (field (name "MANUFACTURER") "Rohm")
        (field (name "MANUFACTURER PART NUMBER") "ESR10EZPF1001")
        (field (name "SUPPLIER PART NUMBER 1") "755-ESR10EZPF1001")
      )
      (libsource (lib "interface_Schlib") (part "ESR10EZPF1001"))
    )
    (comp (ref "R59")
      (value "10kOhm")
      (footprint "FP-ESR10-IPC_A")
      (description "Res Thick Film 0805 10K Ohm 1% 0.4W ±100ppm/C Pad SMD Automotive T/R")
      (fields
        (field (name "MANUFACTURER") "Rohm")
        (field (name "MANUFACTURER PART NUMBER") "ESR10EZPF1002")
        (field (name "SUPPLIER PART NUMBER 1") "755-ESR10EZPF1002")
      )
      (libsource (lib "interface_Schlib") (part "ESR10EZPF1002"))
    )
    (comp (ref "R61")
      (value "52.3kOhm")
      (footprint "FP-KTR10-IPC_A")
      (description "Res High Voltage 0805 52.3K Ohm 1/8W 1% SMD")
      (fields
        (field (name "MANUFACTURER") "Rohm")
        (field (name "MANUFACTURER PART NUMBER") "KTR10EZPF5232")
        (field (name "SUPPLIER PART NUMBER 1") "755-KTR10EZPF5232")
      )
      (libsource (lib "interface_Schlib") (part "KTR10EZPF5232"))
    )
    (comp (ref "R62")
      (value "10kOhm")
      (footprint "FP-ESR10-IPC_A")
      (description "Res Thick Film 0805 10K Ohm 1% 0.4W ±100ppm/C Pad SMD Automotive T/R")
      (fields
        (field (name "MANUFACTURER") "Rohm")
        (field (name "MANUFACTURER PART NUMBER") "ESR10EZPF1002")
        (field (name "SUPPLIER PART NUMBER 1") "755-ESR10EZPF1002")
      )
      (libsource (lib "interface_Schlib") (part "ESR10EZPF1002"))
    )
    (comp (ref "R510")
      (value "100kOhm")
      (footprint "FP-ESR10-IPC_A")
      (description "Res Thick Film 0805 100K Ohm 1% 0.4W ±100ppm/C Epoxy Resin Pad SMD Automotive T/R")
      (fields
        (field (name "MANUFACTURER") "Rohm")
        (field (name "MANUFACTURER PART NUMBER") "ESR10EZPF1003")
        (field (name "SUPPLIER PART NUMBER 1") "755-ESR10EZPF1003")
      )
      (libsource (lib "interface_Schlib") (part "ESR10EZPF1003"))
    )
    (comp (ref "R511")
      (value "100Ohm")
      (footprint "FP-ESR10-IPC_A")
      (description "Res Thick Film 0805 100 Ohm 1% 2/5W ±100ppm/°C Molded SMD Paper T/R")
      (fields
        (field (name "MANUFACTURER") "Rohm")
        (field (name "MANUFACTURER PART NUMBER") "ESR10EZPF1000")
        (field (name "SUPPLIER PART NUMBER 1") "755-ESR10EZPF1000")
      )
      (libsource (lib "interface_Schlib") (part "ESR10EZPF1000"))
    )
    (comp (ref "R512")
      (value "1kOhm")
      (footprint "FP-ESR10-IPC_A")
      (description "Res Thick Film 0805 1K Ohm 1% 0.4W ±100ppm/C Epoxy Resin Pad SMD Automotive T/R")
      (fields
        (field (name "MANUFACTURER") "Rohm")
        (field (name "MANUFACTURER PART NUMBER") "ESR10EZPF1001")
        (field (name "SUPPLIER PART NUMBER 1") "755-ESR10EZPF1001")
      )
      (libsource (lib "interface_Schlib") (part "ESR10EZPF1001"))
    )
    (comp (ref "R513")
      (value "1kOhm")
      (footprint "FP-ESR10-IPC_A")
      (description "Res Thick Film 0805 1K Ohm 1% 0.4W ±100ppm/C Epoxy Resin Pad SMD Automotive T/R")
      (fields
        (field (name "MANUFACTURER") "Rohm")
        (field (name "MANUFACTURER PART NUMBER") "ESR10EZPF1001")
        (field (name "SUPPLIER PART NUMBER 1") "755-ESR10EZPF1001")
      )
      (libsource (lib "interface_Schlib") (part "ESR10EZPF1001"))
    )
    (comp (ref "R514")
      (value "820Ohm")
      (footprint "FP-ESR10-IPC_A")
      (description "Res Thick Film 0805 820 Ohm 5% 0.4W ±200ppm/C Epoxy Resin Pad SMD Automotive T/R")
      (fields
        (field (name "MANUFACTURER") "Rohm")
        (field (name "MANUFACTURER PART NUMBER") "ESR10EZPJ821")
        (field (name "SUPPLIER PART NUMBER 1") "755-ESR10EZPJ821")
      )
      (libsource (lib "interface_Schlib") (part "ESR10EZPJ821"))
    )
    (comp (ref "R515")
      (value "1kOhm")
      (footprint "FP-ESR10-IPC_A")
      (description "Res Thick Film 0805 1K Ohm 1% 0.4W ±100ppm/C Epoxy Resin Pad SMD Automotive T/R")
      (fields
        (field (name "MANUFACTURER") "Rohm")
        (field (name "MANUFACTURER PART NUMBER") "ESR10EZPF1001")
        (field (name "SUPPLIER PART NUMBER 1") "755-ESR10EZPF1001")
      )
      (libsource (lib "interface_Schlib") (part "ESR10EZPF1001"))
    )
    (comp (ref "R516")
      (value "10kOhm")
      (footprint "FP-ESR10-IPC_A")
      (description "Res Thick Film 0805 10K Ohm 1% 0.4W ±100ppm/C Pad SMD Automotive T/R")
      (fields
        (field (name "MANUFACTURER") "Rohm")
        (field (name "MANUFACTURER PART NUMBER") "ESR10EZPF1002")
        (field (name "SUPPLIER PART NUMBER 1") "755-ESR10EZPF1002")
      )
      (libsource (lib "interface_Schlib") (part "ESR10EZPF1002"))
    )
    (comp (ref "R517")
      (value "100kOhm")
      (footprint "FP-ESR10-IPC_A")
      (description "Res Thick Film 0805 100K Ohm 1% 0.4W ±100ppm/C Epoxy Resin Pad SMD Automotive T/R")
      (fields
        (field (name "MANUFACTURER") "Rohm")
        (field (name "MANUFACTURER PART NUMBER") "ESR10EZPF1003")
        (field (name "SUPPLIER PART NUMBER 1") "755-ESR10EZPF1003")
      )
      (libsource (lib "interface_Schlib") (part "ESR10EZPF1003"))
    )
    (comp (ref "R518")
      (value "100Ohm")
      (footprint "FP-ESR10-IPC_A")
      (description "Res Thick Film 0805 100 Ohm 1% 2/5W ±100ppm/°C Molded SMD Paper T/R")
      (fields
        (field (name "MANUFACTURER") "Rohm")
        (field (name "MANUFACTURER PART NUMBER") "ESR10EZPF1000")
        (field (name "SUPPLIER PART NUMBER 1") "755-ESR10EZPF1000")
      )
      (libsource (lib "interface_Schlib") (part "ESR10EZPF1000"))
    )
    (comp (ref "R519")
      (value "1kOhm")
      (footprint "FP-ESR10-IPC_A")
      (description "Res Thick Film 0805 1K Ohm 1% 0.4W ±100ppm/C Epoxy Resin Pad SMD Automotive T/R")
      (fields
        (field (name "MANUFACTURER") "Rohm")
        (field (name "MANUFACTURER PART NUMBER") "ESR10EZPF1001")
        (field (name "SUPPLIER PART NUMBER 1") "755-ESR10EZPF1001")
      )
      (libsource (lib "interface_Schlib") (part "ESR10EZPF1001"))
    )
    (comp (ref "R520")
      (value "1kOhm")
      (footprint "FP-ESR10-IPC_A")
      (description "Res Thick Film 0805 1K Ohm 1% 0.4W ±100ppm/C Epoxy Resin Pad SMD Automotive T/R")
      (fields
        (field (name "MANUFACTURER") "Rohm")
        (field (name "MANUFACTURER PART NUMBER") "ESR10EZPF1001")
        (field (name "SUPPLIER PART NUMBER 1") "755-ESR10EZPF1001")
      )
      (libsource (lib "interface_Schlib") (part "ESR10EZPF1001"))
    )
    (comp (ref "R521")
      (value "820Ohm")
      (footprint "FP-ESR10-IPC_A")
      (description "Res Thick Film 0805 820 Ohm 5% 0.4W ±200ppm/C Epoxy Resin Pad SMD Automotive T/R")
      (fields
        (field (name "MANUFACTURER") "Rohm")
        (field (name "MANUFACTURER PART NUMBER") "ESR10EZPJ821")
        (field (name "SUPPLIER PART NUMBER 1") "755-ESR10EZPJ821")
      )
      (libsource (lib "interface_Schlib") (part "ESR10EZPJ821"))
    )
    (comp (ref "R522")
      (value "1kOhm")
      (footprint "FP-ESR10-IPC_A")
      (description "Res Thick Film 0805 1K Ohm 1% 0.4W ±100ppm/C Epoxy Resin Pad SMD Automotive T/R")
      (fields
        (field (name "MANUFACTURER") "Rohm")
        (field (name "MANUFACTURER PART NUMBER") "ESR10EZPF1001")
        (field (name "SUPPLIER PART NUMBER 1") "755-ESR10EZPF1001")
      )
      (libsource (lib "interface_Schlib") (part "ESR10EZPF1001"))
    )
    (comp (ref "R523")
      (value "10kOhm")
      (footprint "FP-ESR10-IPC_A")
      (description "Res Thick Film 0805 10K Ohm 1% 0.4W ±100ppm/C Pad SMD Automotive T/R")
      (fields
        (field (name "MANUFACTURER") "Rohm")
        (field (name "MANUFACTURER PART NUMBER") "ESR10EZPF1002")
        (field (name "SUPPLIER PART NUMBER 1") "755-ESR10EZPF1002")
      )
      (libsource (lib "interface_Schlib") (part "ESR10EZPF1002"))
    )
    (comp (ref "R524")
      (value "100kOhm")
      (footprint "FP-ESR10-IPC_A")
      (description "Res Thick Film 0805 100K Ohm 1% 0.4W ±100ppm/C Epoxy Resin Pad SMD Automotive T/R")
      (fields
        (field (name "MANUFACTURER") "Rohm")
        (field (name "MANUFACTURER PART NUMBER") "ESR10EZPF1003")
        (field (name "SUPPLIER PART NUMBER 1") "755-ESR10EZPF1003")
      )
      (libsource (lib "interface_Schlib") (part "ESR10EZPF1003"))
    )
    (comp (ref "R525")
      (value "100Ohm")
      (footprint "FP-ESR10-IPC_A")
      (description "Res Thick Film 0805 100 Ohm 1% 2/5W ±100ppm/°C Molded SMD Paper T/R")
      (fields
        (field (name "MANUFACTURER") "Rohm")
        (field (name "MANUFACTURER PART NUMBER") "ESR10EZPF1000")
        (field (name "SUPPLIER PART NUMBER 1") "755-ESR10EZPF1000")
      )
      (libsource (lib "interface_Schlib") (part "ESR10EZPF1000"))
    )
    (comp (ref "R526")
      (value "1kOhm")
      (footprint "FP-ESR10-IPC_A")
      (description "Res Thick Film 0805 1K Ohm 1% 0.4W ±100ppm/C Epoxy Resin Pad SMD Automotive T/R")
      (fields
        (field (name "MANUFACTURER") "Rohm")
        (field (name "MANUFACTURER PART NUMBER") "ESR10EZPF1001")
        (field (name "SUPPLIER PART NUMBER 1") "755-ESR10EZPF1001")
      )
      (libsource (lib "interface_Schlib") (part "ESR10EZPF1001"))
    )
    (comp (ref "R527")
      (value "1kOhm")
      (footprint "FP-ESR10-IPC_A")
      (description "Res Thick Film 0805 1K Ohm 1% 0.4W ±100ppm/C Epoxy Resin Pad SMD Automotive T/R")
      (fields
        (field (name "MANUFACTURER") "Rohm")
        (field (name "MANUFACTURER PART NUMBER") "ESR10EZPF1001")
        (field (name "SUPPLIER PART NUMBER 1") "755-ESR10EZPF1001")
      )
      (libsource (lib "interface_Schlib") (part "ESR10EZPF1001"))
    )
    (comp (ref "R528")
      (value "820Ohm")
      (footprint "FP-ESR10-IPC_A")
      (description "Res Thick Film 0805 820 Ohm 5% 0.4W ±200ppm/C Epoxy Resin Pad SMD Automotive T/R")
      (fields
        (field (name "MANUFACTURER") "Rohm")
        (field (name "MANUFACTURER PART NUMBER") "ESR10EZPJ821")
        (field (name "SUPPLIER PART NUMBER 1") "755-ESR10EZPJ821")
      )
      (libsource (lib "interface_Schlib") (part "ESR10EZPJ821"))
    )
    (comp (ref "U21")
      (value "TC4051BFTELN")
      (footprint "FP-TC4051BFTELN")
      (description "Analog Multiplexer Single 8: 1 16-Pin TSSOP T/R")
      (fields
        (field (name "MANUFACTURER") "Toshiba")
        (field (name "SUPPLIER PART NUMBER 1") "757-TC4051BFTELN")
      )
      (libsource (lib "interface_Schlib") (part "TC4051BFTELN"))
    )
    (comp (ref "U22")
      (value "TC4051BFTELN")
      (footprint "FP-TC4051BFTELN")
      (description "Analog Multiplexer Single 8: 1 16-Pin TSSOP T/R")
      (fields
        (field (name "MANUFACTURER") "Toshiba")
        (field (name "SUPPLIER PART NUMBER 1") "757-TC4051BFTELN")
      )
      (libsource (lib "interface_Schlib") (part "TC4051BFTELN"))
    )
    (comp (ref "U23")
      (value "SN74LV1T02DBVRG4")
      (footprint "FP-DBV0005A-IPC_A")
      (description "Single Power Supply 2-input POSITIVE NOR GATE Logic Level Shifter 5-SOT-23 -40 to 125")
      (fields
        (field (name "MANUFACTURER") "Texas Instruments")
        (field (name "SUPPLIER PART NUMBER 1") "595-SN74LV1T02DBVRG4")
      )
      (libsource (lib "interface_Schlib") (part "SN74LV1T02DBVRG4"))
    )
    (comp (ref "U24")
      (value "SN74LV1T02DBVRG4")
      (footprint "FP-DBV0005A-IPC_A")
      (description "Single Power Supply 2-input POSITIVE NOR GATE Logic Level Shifter 5-SOT-23 -40 to 125")
      (fields
        (field (name "MANUFACTURER") "Texas Instruments")
        (field (name "SUPPLIER PART NUMBER 1") "595-SN74LV1T02DBVRG4")
      )
      (libsource (lib "") (part "SN74LV1T02DBVRG4_1"))
    )
    (comp (ref "U31")
      (value "ADC101C027CIMK/NOPB")
      (footprint "MK06A_N")
      (description "10-Bit, 189kSPS, 1-Ch SAR ADC with I2C 6-SOT-23-THIN -40 to 105")
      (fields
        (field (name "MANUFACTURER") "TI National Semiconductor")
        (field (name "SUPPLIER PART NUMBER 1") "926-AD101C027CIMKNPB")
      )
      (libsource (lib "interface_Schlib") (part "ADC101C027CIMK/NOPB"))
    )
    (comp (ref "U61")
      (value "AP62301WU-7")
      (footprint "TSOP95P280X100-6N")
      (description "Converter DC to DC 4.2V to 18V Synchronous Step Down Single-Out 3A 6-Pin TSOT-26 T/R")
      (fields
        (field (name "MANUFACTURER") "Diodes")
        (field (name "SUPPLIER PART NUMBER 1") "621-AP62301WU-7")
      )
      (libsource (lib "interface_Schlib") (part "AP62301WU-7"))
    )
  )
  (nets
    (net (code "1") (name "+3V3") (class "Default")
      (node (ref "C32") (pin "2") (pinfunction "2_2") (pintype "passive"))
      (node (ref "C33") (pin "2") (pinfunction "2_2") (pintype "passive"))
      (node (ref "C34") (pin "2") (pinfunction "2_2") (pintype "passive"))
      (node (ref "C510") (pin "2") (pinfunction "2_2") (pintype "passive"))
      (node (ref "C54") (pin "2") (pinfunction "2_2") (pintype "passive"))
      (node (ref "J12") (pin "17") (pinfunction "17_17") (pintype "passive"))
      (node (ref "J12") (pin "19") (pinfunction "19_19") (pintype "passive"))
      (node (ref "J12") (pin "5") (pinfunction "5_5") (pintype "passive"))
      (node (ref "J12") (pin "7") (pinfunction "7_7") (pintype "passive"))
      (node (ref "J12") (pin "9") (pinfunction "9_9") (pintype "passive"))
      (node (ref "J13") (pin "3") (pinfunction "3_3") (pintype "passive"))
      (node (ref "J32") (pin "2") (pinfunction "2_2") (pintype "passive"))
      (node (ref "J33") (pin "1") (pinfunction "1_1") (pintype "passive"))
      (node (ref "J52") (pin "1") (pinfunction "1_1") (pintype "passive"))
      (node (ref "J54") (pin "1") (pinfunction "1_1") (pintype "passive"))
      (node (ref "Q54") (pin "3") (pinfunction "3_3") (pintype "passive"))
      (node (ref "Q56") (pin "3") (pinfunction "3_3") (pintype "passive"))
      (node (ref "R510") (pin "2") (pinfunction "2_2") (pintype "passive"))
      (node (ref "R517") (pin "2") (pinfunction "2_2") (pintype "passive"))
      (node (ref "R524") (pin "2") (pinfunction "2_2") (pintype "passive"))
      (node (ref "R53") (pin "2") (pinfunction "2_2") (pintype "passive"))
      (node (ref "U31") (pin "1") (pinfunction "VA_1") (pintype "power_in"))
    )
    (net (code "2") (name "+3V3_NFC") (class "Default")
      (node (ref "C511") (pin "2") (pinfunction "2_2") (pintype "passive"))
      (node (ref "J31") (pin "1") (pinfunction "1_1") (pintype "passive"))
      (node (ref "J54") (pin "2") (pinfunction "2_2") (pintype "passive"))
      (node (ref "Q56") (pin "2") (pinfunction "2_2") (pintype "passive"))
    )
    (net (code "3") (name "+3V3_US") (class "Default")
      (node (ref "C24") (pin "2") (pinfunction "2_2") (pintype "passive"))
      (node (ref "C55") (pin "2") (pinfunction "2_2") (pintype "passive"))
      (node (ref "J52") (pin "2") (pinfunction "2_2") (pintype "passive"))
      (node (ref "Q54") (pin "2") (pinfunction "2_2") (pintype "passive"))
      (node (ref "U24") (pin "5") (pinfunction "VCC_5") (pintype "passive"))
    )
    (net (code "4") (name "+5V") (class "Default")
      (node (ref "C51") (pin "2") (pinfunction "2_2") (pintype "passive"))
      (node (ref "C57") (pin "2") (pinfunction "2_2") (pintype "passive"))
      (node (ref "J12") (pin "2") (pinfunction "2_2") (pintype "passive"))
      (node (ref "J12") (pin "4") (pinfunction "4_4") (pintype "passive"))
      (node (ref "J12") (pin "6") (pinfunction "6_6") (pintype "passive"))
      (node (ref "J51") (pin "1") (pinfunction "1_1") (pintype "passive"))
      (node (ref "J53") (pin "1") (pinfunction "1_1") (pintype "passive"))
      (node (ref "Q53") (pin "3") (pinfunction "3_3") (pintype "passive"))
      (node (ref "Q55") (pin "3") (pinfunction "3_3") (pintype "passive"))
      (node (ref "R41") (pin "2") (pinfunction "2_2") (pintype "passive"))
      (node (ref "R42") (pin "2") (pinfunction "2_2") (pintype "passive"))
      (node (ref "R43") (pin "2") (pinfunction "2_2") (pintype "passive"))
    )
    (net (code "5") (name "+5V_GSM") (class "Default")
      (node (ref "C11") (pin "2") (pinfunction "2_2") (pintype "passive"))
      (node (ref "C12") (pin "2") (pinfunction "2_2") (pintype "passive"))
      (node (ref "C13") (pin "2") (pinfunction "2_2") (pintype "passive"))
      (node (ref "C58") (pin "2") (pinfunction "2_2") (pintype "passive"))
      (node (ref "J13") (pin "1") (pinfunction "1_1") (pintype "passive"))
      (node (ref "J53") (pin "2") (pinfunction "2_2") (pintype "passive"))
      (node (ref "Q55") (pin "2") (pinfunction "2_2") (pintype "passive"))
    )
    (net (code "6") (name "+5V_US") (class "Default")
      (node (ref "C21") (pin "2") (pinfunction "2_2") (pintype "passive"))
      (node (ref "C22") (pin "2") (pinfunction "2_2") (pintype "passive"))
      (node (ref "C23") (pin "2") (pinfunction "2_2") (pintype "passive"))
      (node (ref "C52") (pin "2") (pinfunction "2_2") (pintype "passive"))
      (node (ref "J21") (pin "1") (pinfunction "1_1") (pintype "passive"))
      (node (ref "J22") (pin "1") (pinfunction "1_1") (pintype "passive"))
      (node (ref "J23") (pin "1") (pinfunction "1_1") (pintype "passive"))
      (node (ref "J24") (pin "1") (pinfunction "1_1") (pintype "passive"))
      (node (ref "J25") (pin "1") (pinfunction "1_1") (pintype "passive"))
      (node (ref "J51") (pin "2") (pinfunction "2_2") (pintype "passive"))
      (node (ref "Q53") (pin "2") (pinfunction "2_2") (pintype "passive"))
      (node (ref "U21") (pin "16") (pinfunction "VDD_16") (pintype "passive"))
      (node (ref "U22") (pin "16") (pinfunction "VDD_16") (pintype "passive"))
      (node (ref "U23") (pin "5") (pinfunction "VCC_5") (pintype "passive"))
    )
    (net (code "7") (name "+5V_ZYBO") (class "Default")
      (node (ref "C621") (pin "2") (pinfunction "2_2") (pintype "passive"))
      (node (ref "C622") (pin "2") (pinfunction "2_2") (pintype "passive"))
      (node (ref "J01") (pin "1") (pinfunction "1_1") (pintype "passive"))
      (node (ref "L61") (pin "2") (pinfunction "2_2") (pintype "passive"))
      (node (ref "R44") (pin "2") (pinfunction "2_2") (pintype "passive"))
      (node (ref "R61") (pin "2") (pinfunction "2_2") (pintype "passive"))
    )
    (net (code "8") (name "+12V") (class "Default")
      (node (ref "C61") (pin "2") (pinfunction "2_2") (pintype "passive"))
      (node (ref "J12") (pin "14") (pinfunction "14_14") (pintype "passive"))
      (node (ref "J12") (pin "16") (pinfunction "16_16") (pintype "passive"))
      (node (ref "J12") (pin "18") (pinfunction "18_18") (pintype "passive"))
      (node (ref "R31") (pin "2") (pinfunction "2_2") (pintype "passive"))
      (node (ref "R516") (pin "1") (pinfunction "1_1") (pintype "passive"))
      (node (ref "R52") (pin "1") (pinfunction "1_1") (pintype "passive"))
      (node (ref "R523") (pin "1") (pinfunction "1_1") (pintype "passive"))
      (node (ref "R59") (pin "1") (pinfunction "1_1") (pintype "passive"))
      (node (ref "U61") (pin "3") (pinfunction "3_3") (pintype "passive"))
    )
    (net (code "9") (name "/BALISE_I2C_SCL") (class "Default")
      (node (ref "J33") (pin "4") (pinfunction "4_4") (pintype "passive"))
      (node (ref "J34") (pin "2") (pinfunction "2_2") (pintype "passive"))
    )
    (net (code "10") (name "/BALISE_I2C_SDA") (class "Default")
      (node (ref "J33") (pin "3") (pinfunction "3_3") (pintype "passive"))
      (node (ref "J34") (pin "9") (pinfunction "9_9") (pintype "passive"))
    )
    (net (code "11") (name "/BAT_ALERT") (class "Default")
      (node (ref "J14") (pin "1") (pinfunction "1_1") (pintype "passive"))
      (node (ref "R47") (pin "1") (pinfunction "1_1") (pintype "passive"))
    )
    (net (code "12") (name "/BAT_I2C_SCL") (class "Default")
      (node (ref "J14") (pin "3") (pinfunction "3_3") (pintype "passive"))
      (node (ref "U31") (pin "5") (pinfunction "SCL_5") (pintype "input"))
    )
    (net (code "13") (name "/BAT_I2C_SDA") (class "Default")
      (node (ref "J14") (pin "9") (pinfunction "9_9") (pintype "passive"))
      (node (ref "U31") (pin "6") (pinfunction "SDA_6") (pintype "bidirectional"))
    )
    (net (code "14") (name "/GSM_RST") (class "Default")
      (node (ref "J13") (pin "7") (pinfunction "7_7") (pintype "passive"))
      (node (ref "J14") (pin "8") (pinfunction "8_8") (pintype "passive"))
    )
    (net (code "15") (name "/GSM_UART_RXD") (class "Default")
      (node (ref "J13") (pin "5") (pinfunction "5_5") (pintype "passive"))
      (node (ref "J14") (pin "2") (pinfunction "2_2") (pintype "passive"))
    )
    (net (code "16") (name "/GSM_UART_TXD") (class "Default")
      (node (ref "J13") (pin "4") (pinfunction "4_4") (pintype "passive"))
      (node (ref "J14") (pin "7") (pinfunction "7_7") (pintype "passive"))
    )
    (net (code "17") (name "/HOLO_LED_DEBUG") (class "Default")
      (node (ref "J11") (pin "16") (pinfunction "16_16") (pintype "passive"))
      (node (ref "R46") (pin "1") (pinfunction "1_1") (pintype "passive"))
    )
    (net (code "18") (name "/HOLO_LED_PWR") (class "Default")
      (node (ref "J11") (pin "14") (pinfunction "14_14") (pintype "passive"))
      (node (ref "R45") (pin "1") (pinfunction "1_1") (pintype "passive"))
    )
    (net (code "19") (name "/HOLO_UART_RX") (class "Default")
      (node (ref "J11") (pin "1") (pinfunction "1_1") (pintype "passive"))
      (node (ref "J14") (pin "4") (pinfunction "4_4") (pintype "passive"))
    )
    (net (code "20") (name "/HOLO_UART_TX") (class "Default")
      (node (ref "J11") (pin "3") (pinfunction "3_3") (pintype "passive"))
      (node (ref "J14") (pin "10") (pinfunction "10_10") (pintype "passive"))
    )
    (net (code "21") (name "/IMU_I2C_SCL") (class "Default")
      (node (ref "J32") (pin "4") (pinfunction "4_4") (pintype "passive"))
      (node (ref "J34") (pin "3") (pinfunction "3_3") (pintype "passive"))
    )
    (net (code "22") (name "/IMU_I2C_SDA") (class "Default")
      (node (ref "J32") (pin "3") (pinfunction "3_3") (pintype "passive"))
      (node (ref "J34") (pin "4") (pinfunction "4_4") (pintype "passive"))
    )
    (net (code "23") (name "/NFC_FD") (class "Default")
      (node (ref "J31") (pin "3") (pinfunction "3_3") (pintype "passive"))
      (node (ref "J34") (pin "8") (pinfunction "8_8") (pintype "passive"))
    )
    (net (code "24") (name "/NFC_I2C_SCL") (class "Default")
      (node (ref "J31") (pin "5") (pinfunction "5_5") (pintype "passive"))
      (node (ref "J34") (pin "7") (pinfunction "7_7") (pintype "passive"))
    )
    (net (code "25") (name "/NFC_I2C_SDA") (class "Default")
      (node (ref "J31") (pin "4") (pinfunction "4_4") (pintype "passive"))
      (node (ref "J34") (pin "1") (pinfunction "1_1") (pintype "passive"))
    )
    (net (code "26") (name "/PWR_MGT_GSM") (class "Default")
      (node (ref "J26") (pin "4") (pinfunction "4_4") (pintype "passive"))
      (node (ref "R518") (pin "1") (pinfunction "1_1") (pintype "passive"))
    )
    (net (code "27") (name "/PWR_MGT_NFC") (class "Default")
      (node (ref "J26") (pin "10") (pinfunction "10_10") (pintype "passive"))
      (node (ref "R525") (pin "1") (pinfunction "1_1") (pintype "passive"))
    )
    (net (code "28") (name "/PWR_MGT_US") (class "Default")
      (node (ref "J26") (pin "9") (pinfunction "9_9") (pintype "passive"))
      (node (ref "R511") (pin "1") (pinfunction "1_1") (pintype "passive"))
      (node (ref "R54") (pin "1") (pinfunction "1_1") (pintype "passive"))
    )
    (net (code "29") (name "/US_1_ECHO_5V") (class "Default")
      (node (ref "J21") (pin "3") (pinfunction "3_3") (pintype "passive"))
      (node (ref "U22") (pin "12") (pinfunction "3_12") (pintype "passive"))
    )
    (net (code "30") (name "/US_1_TRIG_5V") (class "Default")
      (node (ref "J21") (pin "2") (pinfunction "2_2") (pintype "passive"))
      (node (ref "U21") (pin "12") (pinfunction "3_12") (pintype "passive"))
    )
    (net (code "31") (name "/US_2_ECHO_5V") (class "Default")
      (node (ref "J22") (pin "3") (pinfunction "3_3") (pintype "passive"))
      (node (ref "U22") (pin "13") (pinfunction "0_13") (pintype "passive"))
    )
    (net (code "32") (name "/US_2_TRIG_5V") (class "Default")
      (node (ref "J22") (pin "2") (pinfunction "2_2") (pintype "passive"))
      (node (ref "U21") (pin "13") (pinfunction "0_13") (pintype "passive"))
    )
    (net (code "33") (name "/US_3_ECHO_5V") (class "Default")
      (node (ref "J23") (pin "3") (pinfunction "3_3") (pintype "passive"))
      (node (ref "U22") (pin "14") (pinfunction "1_14") (pintype "passive"))
    )
    (net (code "34") (name "/US_3_TRIG_5V") (class "Default")
      (node (ref "J23") (pin "2") (pinfunction "2_2") (pintype "passive"))
      (node (ref "U21") (pin "14") (pinfunction "1_14") (pintype "passive"))
    )
    (net (code "35") (name "/US_4_ECHO_5V") (class "Default")
      (node (ref "J24") (pin "3") (pinfunction "3_3") (pintype "passive"))
      (node (ref "U22") (pin "15") (pinfunction "2_15") (pintype "passive"))
    )
    (net (code "36") (name "/US_4_TRIG_5V") (class "Default")
      (node (ref "J24") (pin "2") (pinfunction "2_2") (pintype "passive"))
      (node (ref "U21") (pin "15") (pinfunction "2_15") (pintype "passive"))
    )
    (net (code "37") (name "/US_5_ECHO_5V") (class "Default")
      (node (ref "J25") (pin "3") (pinfunction "3_3") (pintype "passive"))
      (node (ref "U22") (pin "1") (pinfunction "4_1") (pintype "passive"))
    )
    (net (code "38") (name "/US_5_TRIG_5V") (class "Default")
      (node (ref "J25") (pin "2") (pinfunction "2_2") (pintype "passive"))
      (node (ref "U21") (pin "1") (pinfunction "4_1") (pintype "passive"))
    )
    (net (code "39") (name "/US_ECHO_3V3") (class "Default")
      (node (ref "J26") (pin "8") (pinfunction "8_8") (pintype "passive"))
      (node (ref "R25") (pin "2") (pinfunction "2_2") (pintype "passive"))
    )
    (net (code "40") (name "/US_ECHO_5V") (class "Default")
      (node (ref "U22") (pin "3") (pinfunction "COM_3") (pintype "passive"))
      (node (ref "U24") (pin "1") (pinfunction "1_1") (pintype "passive"))
      (node (ref "U24") (pin "2") (pinfunction "2_2") (pintype "passive"))
    )
    (net (code "41") (name "/US_SEL_0") (class "Default")
      (node (ref "J26") (pin "1") (pinfunction "1_1") (pintype "passive"))
      (node (ref "R21") (pin "2") (pinfunction "2_2") (pintype "passive"))
    )
    (net (code "42") (name "/US_SEL_1") (class "Default")
      (node (ref "J26") (pin "2") (pinfunction "2_2") (pintype "passive"))
      (node (ref "R22") (pin "2") (pinfunction "2_2") (pintype "passive"))
    )
    (net (code "43") (name "/US_SEL_2") (class "Default")
      (node (ref "J26") (pin "3") (pinfunction "3_3") (pintype "passive"))
      (node (ref "R23") (pin "2") (pinfunction "2_2") (pintype "passive"))
    )
    (net (code "44") (name "/US_TRIG_3V3") (class "Default")
      (node (ref "J26") (pin "7") (pinfunction "7_7") (pintype "passive"))
      (node (ref "R24") (pin "1") (pinfunction "1_1") (pintype "passive"))
    )
    (net (code "45") (name "/US_TRIG_5V") (class "Default")
      (node (ref "U21") (pin "3") (pinfunction "COM_3") (pintype "passive"))
      (node (ref "U23") (pin "4") (pinfunction "4_4") (pintype "passive"))
    )
    (net (code "46") (name "GND") (class "Default")
      (node (ref "C11") (pin "1") (pinfunction "1_1") (pintype "passive"))
      (node (ref "C12") (pin "1") (pinfunction "1_1") (pintype "passive"))
      (node (ref "C13") (pin "1") (pinfunction "1_1") (pintype "passive"))
      (node (ref "C21") (pin "1") (pinfunction "1_1") (pintype "passive"))
      (node (ref "C22") (pin "1") (pinfunction "1_1") (pintype "passive"))
      (node (ref "C23") (pin "1") (pinfunction "1_1") (pintype "passive"))
      (node (ref "C24") (pin "1") (pinfunction "1_1") (pintype "passive"))
      (node (ref "C31") (pin "1") (pinfunction "1_1") (pintype "passive"))
      (node (ref "C32") (pin "1") (pinfunction "1_1") (pintype "passive"))
      (node (ref "C33") (pin "1") (pinfunction "1_1") (pintype "passive"))
      (node (ref "C34") (pin "1") (pinfunction "1_1") (pintype "passive"))
      (node (ref "C512") (pin "1") (pinfunction "1_1") (pintype "passive"))
      (node (ref "C53") (pin "1") (pinfunction "1_1") (pintype "passive"))
      (node (ref "C56") (pin "1") (pinfunction "1_1") (pintype "passive"))
      (node (ref "C59") (pin "1") (pinfunction "1_1") (pintype "passive"))
      (node (ref "C61") (pin "1") (pinfunction "1_1") (pintype "passive"))
      (node (ref "C621") (pin "1") (pinfunction "1_1") (pintype "passive"))
      (node (ref "C622") (pin "1") (pinfunction "1_1") (pintype "passive"))
      (node (ref "D4") (pin "1") (pinfunction "1_1") (pintype "passive"))
      (node (ref "J01") (pin "2") (pinfunction "2_2") (pintype "passive"))
      (node (ref "J01") (pin "3") (pinfunction "3_3") (pintype "passive"))
      (node (ref "J11") (pin "10") (pinfunction "10_10") (pintype "passive"))
      (node (ref "J11") (pin "12") (pinfunction "12_12") (pintype "passive"))
      (node (ref "J11") (pin "13") (pinfunction "13_13") (pintype "passive"))
      (node (ref "J11") (pin "15") (pinfunction "15_15") (pintype "passive"))
      (node (ref "J11") (pin "18") (pinfunction "18_18") (pintype "passive"))
      (node (ref "J11") (pin "20") (pinfunction "20_20") (pintype "passive"))
      (node (ref "J11") (pin "5") (pinfunction "5_5") (pintype "passive"))
      (node (ref "J11") (pin "7") (pinfunction "7_7") (pintype "passive"))
      (node (ref "J12") (pin "1") (pinfunction "1_1") (pintype "passive"))
      (node (ref "J12") (pin "10") (pinfunction "10_10") (pintype "passive"))
      (node (ref "J12") (pin "11") (pinfunction "11_11") (pintype "passive"))
      (node (ref "J12") (pin "12") (pinfunction "12_12") (pintype "passive"))
      (node (ref "J12") (pin "13") (pinfunction "13_13") (pintype "passive"))
      (node (ref "J12") (pin "15") (pinfunction "15_15") (pintype "passive"))
      (node (ref "J12") (pin "20") (pinfunction "20_20") (pintype "passive"))
      (node (ref "J12") (pin "3") (pinfunction "3_3") (pintype "passive"))
      (node (ref "J12") (pin "8") (pinfunction "8_8") (pintype "passive"))
      (node (ref "J13") (pin "2") (pinfunction "2_2") (pintype "passive"))
      (node (ref "J13") (pin "6") (pinfunction "6_6") (pintype "passive"))
      (node (ref "J14") (pin "11") (pinfunction "11_11") (pintype "passive"))
      (node (ref "J14") (pin "5") (pinfunction "5_5") (pintype "passive"))
      (node (ref "J21") (pin "4") (pinfunction "4_4") (pintype "passive"))
      (node (ref "J22") (pin "4") (pinfunction "4_4") (pintype "passive"))
      (node (ref "J23") (pin "4") (pinfunction "4_4") (pintype "passive"))
      (node (ref "J24") (pin "4") (pinfunction "4_4") (pintype "passive"))
      (node (ref "J25") (pin "4") (pinfunction "4_4") (pintype "passive"))
      (node (ref "J26") (pin "11") (pinfunction "11_11") (pintype "passive"))
      (node (ref "J26") (pin "5") (pinfunction "5_5") (pintype "passive"))
      (node (ref "J31") (pin "2") (pinfunction "2_2") (pintype "passive"))
      (node (ref "J31") (pin "6") (pinfunction "6_6") (pintype "passive"))
      (node (ref "J32") (pin "1") (pinfunction "1_1") (pintype "passive"))
      (node (ref "J33") (pin "2") (pinfunction "2_2") (pintype "passive"))
      (node (ref "J34") (pin "11") (pinfunction "11_11") (pintype "passive"))
      (node (ref "J34") (pin "5") (pinfunction "5_5") (pintype "passive"))
      (node (ref "Q41") (pin "2") (pinfunction "2_2") (pintype "passive"))
      (node (ref "Q42") (pin "2") (pinfunction "2_2") (pintype "passive"))
      (node (ref "Q43") (pin "2") (pinfunction "2_2") (pintype "passive"))
      (node (ref "R32") (pin "1") (pinfunction "1_1") (pintype "passive"))
      (node (ref "R513") (pin "1") (pinfunction "1_1") (pintype "passive"))
      (node (ref "R514") (pin "1") (pinfunction "1_1") (pintype "passive"))
      (node (ref "R520") (pin "1") (pinfunction "1_1") (pintype "passive"))
      (node (ref "R521") (pin "1") (pinfunction "1_1") (pintype "passive"))
      (node (ref "R527") (pin "1") (pinfunction "1_1") (pintype "passive"))
      (node (ref "R528") (pin "1") (pinfunction "1_1") (pintype "passive"))
      (node (ref "R56") (pin "1") (pinfunction "1_1") (pintype "passive"))
      (node (ref "R57") (pin "1") (pinfunction "1_1") (pintype "passive"))
      (node (ref "R62") (pin "1") (pinfunction "1_1") (pintype "passive"))
      (node (ref "U21") (pin "6") (pinfunction "INH_6") (pintype "passive"))
      (node (ref "U21") (pin "7") (pinfunction "VEE_7") (pintype "passive"))
      (node (ref "U21") (pin "8") (pinfunction "VSS_8") (pintype "passive"))
      (node (ref "U22") (pin "6") (pinfunction "INH_6") (pintype "passive"))
      (node (ref "U22") (pin "7") (pinfunction "VEE_7") (pintype "passive"))
      (node (ref "U22") (pin "8") (pinfunction "VSS_8") (pintype "passive"))
      (node (ref "U23") (pin "3") (pinfunction "GND_3") (pintype "passive"))
      (node (ref "U24") (pin "3") (pinfunction "GND_3") (pintype "passive"))
      (node (ref "U31") (pin "2") (pinfunction "GND_2") (pintype "power_in"))
      (node (ref "U61") (pin "1") (pinfunction "1_1") (pintype "passive"))
    )
    (net (code "47") (name "Net-(C63-Pad1)") (class "Default")
      (node (ref "C63") (pin "1") (pinfunction "1_1") (pintype "passive"))
      (node (ref "U61") (pin "4") (pinfunction "4_4") (pintype "passive"))
    )
    (net (code "48") (name "Net-(C63-Pad2)") (class "Default")
      (node (ref "C63") (pin "2") (pinfunction "2_2") (pintype "passive"))
      (node (ref "L61") (pin "1") (pinfunction "1_1") (pintype "passive"))
      (node (ref "U61") (pin "2") (pinfunction "2_2") (pintype "passive"))
    )
    (net (code "49") (name "Net-(D1-Pad1)") (class "Default")
      (node (ref "D1") (pin "1") (pinfunction "1_1") (pintype "passive"))
      (node (ref "Q41") (pin "3") (pinfunction "3_3") (pintype "passive"))
    )
    (net (code "50") (name "Net-(D1-Pad2)") (class "Default")
      (node (ref "D1") (pin "2") (pinfunction "2_2") (pintype "passive"))
      (node (ref "R41") (pin "1") (pinfunction "1_1") (pintype "passive"))
    )
    (net (code "51") (name "Net-(D2-Pad1)") (class "Default")
      (node (ref "D2") (pin "1") (pinfunction "1_1") (pintype "passive"))
      (node (ref "Q42") (pin "3") (pinfunction "3_3") (pintype "passive"))
    )
    (net (code "52") (name "Net-(D2-Pad2)") (class "Default")
      (node (ref "D2") (pin "2") (pinfunction "2_2") (pintype "passive"))
      (node (ref "R42") (pin "1") (pinfunction "1_1") (pintype "passive"))
    )
    (net (code "53") (name "Net-(D3-Pad1)") (class "Default")
      (node (ref "D3") (pin "1") (pinfunction "1_1") (pintype "passive"))
      (node (ref "Q43") (pin "3") (pinfunction "3_3") (pintype "passive"))
    )
    (net (code "54") (name "Net-(D3-Pad2)") (class "Default")
      (node (ref "D3") (pin "2") (pinfunction "2_2") (pintype "passive"))
      (node (ref "R43") (pin "1") (pinfunction "1_1") (pintype "passive"))
    )
    (net (code "55") (name "Net-(D4-Pad2)") (class "Default")
      (node (ref "D4") (pin "2") (pinfunction "2_2") (pintype "passive"))
      (node (ref "R44") (pin "1") (pinfunction "1_1") (pintype "passive"))
    )
    (net (code "56") (name "Net-(Q41-Pad1)") (class "Default")
      (node (ref "Q41") (pin "1") (pinfunction "1_1") (pintype "passive"))
      (node (ref "R45") (pin "2") (pinfunction "2_2") (pintype "passive"))
    )
    (net (code "57") (name "Net-(Q42-Pad1)") (class "Default")
      (node (ref "Q42") (pin "1") (pinfunction "1_1") (pintype "passive"))
      (node (ref "R46") (pin "2") (pinfunction "2_2") (pintype "passive"))
    )
    (net (code "58") (name "Net-(Q43-Pad1)") (class "Default")
      (node (ref "Q43") (pin "1") (pinfunction "1_1") (pintype "passive"))
      (node (ref "R47") (pin "2") (pinfunction "2_2") (pintype "passive"))
    )
    (net (code "59") (name "Net-(Q51A-B)") (class "Default")
      (node (ref "C53") (pin "2") (pinfunction "2_2") (pintype "passive"))
      (node (ref "Q51") (pin "2") (pinfunction "B_2") (pintype "passive"))
      (node (ref "R55") (pin "2") (pinfunction "2_2") (pintype "passive"))
      (node (ref "R56") (pin "2") (pinfunction "2_2") (pintype "passive"))
    )
    (net (code "60") (name "Net-(Q51A-C)") (class "Default")
      (node (ref "C51") (pin "1") (pinfunction "1_1") (pintype "passive"))
      (node (ref "C52") (pin "1") (pinfunction "1_1") (pintype "passive"))
      (node (ref "Q51") (pin "6") (pinfunction "C_6") (pintype "passive"))
      (node (ref "R51") (pin "1") (pinfunction "1_1") (pintype "passive"))
      (node (ref "R52") (pin "2") (pinfunction "2_2") (pintype "passive"))
    )
    (net (code "61") (name "Net-(Q51A-E)") (class "Default")
      (node (ref "Q51") (pin "1") (pinfunction "E_1") (pintype "passive"))
      (node (ref "R57") (pin "2") (pinfunction "2_2") (pintype "passive"))
    )
    (net (code "62") (name "Net-(Q51B-B)") (class "Default")
      (node (ref "C59") (pin "2") (pinfunction "2_2") (pintype "passive"))
      (node (ref "Q51") (pin "5") (pinfunction "B_5") (pintype "passive"))
      (node (ref "R519") (pin "2") (pinfunction "2_2") (pintype "passive"))
      (node (ref "R520") (pin "2") (pinfunction "2_2") (pintype "passive"))
    )
    (net (code "63") (name "Net-(Q51B-C)") (class "Default")
      (node (ref "C57") (pin "1") (pinfunction "1_1") (pintype "passive"))
      (node (ref "C58") (pin "1") (pinfunction "1_1") (pintype "passive"))
      (node (ref "Q51") (pin "3") (pinfunction "C_3") (pintype "passive"))
      (node (ref "R515") (pin "1") (pinfunction "1_1") (pintype "passive"))
      (node (ref "R516") (pin "2") (pinfunction "2_2") (pintype "passive"))
    )
    (net (code "64") (name "Net-(Q51B-E)") (class "Default")
      (node (ref "Q51") (pin "4") (pinfunction "E_4") (pintype "passive"))
      (node (ref "R521") (pin "2") (pinfunction "2_2") (pintype "passive"))
    )
    (net (code "65") (name "Net-(Q52A-B)") (class "Default")
      (node (ref "C56") (pin "2") (pinfunction "2_2") (pintype "passive"))
      (node (ref "Q52") (pin "2") (pinfunction "B_2") (pintype "passive"))
      (node (ref "R512") (pin "2") (pinfunction "2_2") (pintype "passive"))
      (node (ref "R513") (pin "2") (pinfunction "2_2") (pintype "passive"))
    )
    (net (code "66") (name "Net-(Q52A-C)") (class "Default")
      (node (ref "C54") (pin "1") (pinfunction "1_1") (pintype "passive"))
      (node (ref "C55") (pin "1") (pinfunction "1_1") (pintype "passive"))
      (node (ref "Q52") (pin "6") (pinfunction "C_6") (pintype "passive"))
      (node (ref "R58") (pin "1") (pinfunction "1_1") (pintype "passive"))
      (node (ref "R59") (pin "2") (pinfunction "2_2") (pintype "passive"))
    )
    (net (code "67") (name "Net-(Q52A-E)") (class "Default")
      (node (ref "Q52") (pin "1") (pinfunction "E_1") (pintype "passive"))
      (node (ref "R514") (pin "2") (pinfunction "2_2") (pintype "passive"))
    )
    (net (code "68") (name "Net-(Q52B-B)") (class "Default")
      (node (ref "C512") (pin "2") (pinfunction "2_2") (pintype "passive"))
      (node (ref "Q52") (pin "5") (pinfunction "B_5") (pintype "passive"))
      (node (ref "R526") (pin "2") (pinfunction "2_2") (pintype "passive"))
      (node (ref "R527") (pin "2") (pinfunction "2_2") (pintype "passive"))
    )
    (net (code "69") (name "Net-(Q52B-C)") (class "Default")
      (node (ref "C510") (pin "1") (pinfunction "1_1") (pintype "passive"))
      (node (ref "C511") (pin "1") (pinfunction "1_1") (pintype "passive"))
      (node (ref "Q52") (pin "3") (pinfunction "C_3") (pintype "passive"))
      (node (ref "R522") (pin "1") (pinfunction "1_1") (pintype "passive"))
      (node (ref "R523") (pin "2") (pinfunction "2_2") (pintype "passive"))
    )
    (net (code "70") (name "Net-(Q52B-E)") (class "Default")
      (node (ref "Q52") (pin "4") (pinfunction "E_4") (pintype "passive"))
      (node (ref "R528") (pin "2") (pinfunction "2_2") (pintype "passive"))
    )
    (net (code "71") (name "Net-(Q53-Pad1)") (class "Default")
      (node (ref "Q53") (pin "1") (pinfunction "1_1") (pintype "passive"))
      (node (ref "R51") (pin "2") (pinfunction "2_2") (pintype "passive"))
    )
    (net (code "72") (name "Net-(Q54-Pad1)") (class "Default")
      (node (ref "Q54") (pin "1") (pinfunction "1_1") (pintype "passive"))
      (node (ref "R58") (pin "2") (pinfunction "2_2") (pintype "passive"))
    )
    (net (code "73") (name "Net-(Q55-Pad1)") (class "Default")
      (node (ref "Q55") (pin "1") (pinfunction "1_1") (pintype "passive"))
      (node (ref "R515") (pin "2") (pinfunction "2_2") (pintype "passive"))
    )
    (net (code "74") (name "Net-(Q56-Pad1)") (class "Default")
      (node (ref "Q56") (pin "1") (pinfunction "1_1") (pintype "passive"))
      (node (ref "R522") (pin "2") (pinfunction "2_2") (pintype "passive"))
    )
    (net (code "75") (name "Net-(R24-Pad2)") (class "Default")
      (node (ref "R24") (pin "2") (pinfunction "2_2") (pintype "passive"))
      (node (ref "U23") (pin "1") (pinfunction "1_1") (pintype "passive"))
      (node (ref "U23") (pin "2") (pinfunction "2_2") (pintype "passive"))
    )
    (net (code "76") (name "Net-(R25-Pad1)") (class "Default")
      (node (ref "R25") (pin "1") (pinfunction "1_1") (pintype "passive"))
      (node (ref "U24") (pin "4") (pinfunction "4_4") (pintype "passive"))
    )
    (net (code "77") (name "Net-(R53-Pad1)") (class "Default")
      (node (ref "R53") (pin "1") (pinfunction "1_1") (pintype "passive"))
      (node (ref "R54") (pin "2") (pinfunction "2_2") (pintype "passive"))
      (node (ref "R55") (pin "1") (pinfunction "1_1") (pintype "passive"))
    )
    (net (code "78") (name "Net-(R61-Pad1)") (class "Default")
      (node (ref "R61") (pin "1") (pinfunction "1_1") (pintype "passive"))
      (node (ref "R62") (pin "2") (pinfunction "2_2") (pintype "passive"))
      (node (ref "U61") (pin "6") (pinfunction "6_6") (pintype "passive"))
    )
    (net (code "79") (name "Net-(R510-Pad1)") (class "Default")
      (node (ref "R510") (pin "1") (pinfunction "1_1") (pintype "passive"))
      (node (ref "R511") (pin "2") (pinfunction "2_2") (pintype "passive"))
      (node (ref "R512") (pin "1") (pinfunction "1_1") (pintype "passive"))
    )
    (net (code "80") (name "Net-(R517-Pad1)") (class "Default")
      (node (ref "R517") (pin "1") (pinfunction "1_1") (pintype "passive"))
      (node (ref "R518") (pin "2") (pinfunction "2_2") (pintype "passive"))
      (node (ref "R519") (pin "1") (pinfunction "1_1") (pintype "passive"))
    )
    (net (code "81") (name "Net-(R524-Pad1)") (class "Default")
      (node (ref "R524") (pin "1") (pinfunction "1_1") (pintype "passive"))
      (node (ref "R525") (pin "2") (pinfunction "2_2") (pintype "passive"))
      (node (ref "R526") (pin "1") (pinfunction "1_1") (pintype "passive"))
    )
    (net (code "82") (name "Net-(U21-A)") (class "Default")
      (node (ref "R21") (pin "1") (pinfunction "1_1") (pintype "passive"))
      (node (ref "U21") (pin "11") (pinfunction "A_11") (pintype "passive"))
      (node (ref "U22") (pin "11") (pinfunction "A_11") (pintype "passive"))
    )
    (net (code "83") (name "Net-(U21-B)") (class "Default")
      (node (ref "R22") (pin "1") (pinfunction "1_1") (pintype "passive"))
      (node (ref "U21") (pin "10") (pinfunction "B_10") (pintype "passive"))
      (node (ref "U22") (pin "10") (pinfunction "B_10") (pintype "passive"))
    )
    (net (code "84") (name "Net-(U21-C)") (class "Default")
      (node (ref "R23") (pin "1") (pinfunction "1_1") (pintype "passive"))
      (node (ref "U21") (pin "9") (pinfunction "C_9") (pintype "passive"))
      (node (ref "U22") (pin "9") (pinfunction "C_9") (pintype "passive"))
    )
    (net (code "85") (name "Net-(U31-VIN)") (class "Default")
      (node (ref "C31") (pin "2") (pinfunction "2_2") (pintype "passive"))
      (node (ref "R31") (pin "1") (pinfunction "1_1") (pintype "passive"))
      (node (ref "R32") (pin "2") (pinfunction "2_2") (pintype "passive"))
      (node (ref "U31") (pin "3") (pinfunction "VIN_3") (pintype "input"))
    )
    (net (code "86") (name "unconnected-(J11-Pad2)") (class "Default")
      (node (ref "J11") (pin "2") (pinfunction "2_2") (pintype "passive+no_connect"))
    )
    (net (code "87") (name "unconnected-(J11-Pad4)") (class "Default")
      (node (ref "J11") (pin "4") (pinfunction "4_4") (pintype "passive+no_connect"))
    )
    (net (code "88") (name "unconnected-(J11-Pad6)") (class "Default")
      (node (ref "J11") (pin "6") (pinfunction "6_6") (pintype "passive+no_connect"))
    )
    (net (code "89") (name "unconnected-(J11-Pad8)") (class "Default")
      (node (ref "J11") (pin "8") (pinfunction "8_8") (pintype "passive+no_connect"))
    )
    (net (code "90") (name "unconnected-(J11-Pad9)") (class "Default")
      (node (ref "J11") (pin "9") (pinfunction "9_9") (pintype "passive+no_connect"))
    )
    (net (code "91") (name "unconnected-(J11-Pad11)") (class "Default")
      (node (ref "J11") (pin "11") (pinfunction "11_11") (pintype "passive+no_connect"))
    )
    (net (code "92") (name "unconnected-(J11-Pad17)") (class "Default")
      (node (ref "J11") (pin "17") (pinfunction "17_17") (pintype "passive+no_connect"))
    )
    (net (code "93") (name "unconnected-(J11-Pad19)") (class "Default")
      (node (ref "J11") (pin "19") (pinfunction "19_19") (pintype "passive+no_connect"))
    )
    (net (code "94") (name "unconnected-(J14-Pad6)") (class "Default")
      (node (ref "J14") (pin "6") (pinfunction "6_6") (pintype "passive+no_connect"))
    )
    (net (code "95") (name "unconnected-(J14-Pad12)") (class "Default")
      (node (ref "J14") (pin "12") (pinfunction "12_12") (pintype "passive+no_connect"))
    )
    (net (code "96") (name "unconnected-(J26-Pad6)") (class "Default")
      (node (ref "J26") (pin "6") (pinfunction "6_6") (pintype "passive+no_connect"))
    )
    (net (code "97") (name "unconnected-(J26-Pad12)") (class "Default")
      (node (ref "J26") (pin "12") (pinfunction "12_12") (pintype "passive+no_connect"))
    )
    (net (code "98") (name "unconnected-(J34-Pad6)") (class "Default")
      (node (ref "J34") (pin "6") (pinfunction "6_6") (pintype "passive+no_connect"))
    )
    (net (code "99") (name "unconnected-(J34-Pad10)") (class "Default")
      (node (ref "J34") (pin "10") (pinfunction "10_10") (pintype "passive+no_connect"))
    )
    (net (code "100") (name "unconnected-(J34-Pad12)") (class "Default")
      (node (ref "J34") (pin "12") (pinfunction "12_12") (pintype "passive+no_connect"))
    )
    (net (code "101") (name "unconnected-(U21-6-Pad2)") (class "Default")
      (node (ref "U21") (pin "2") (pinfunction "6_2") (pintype "passive+no_connect"))
    )
    (net (code "102") (name "unconnected-(U21-7-Pad4)") (class "Default")
      (node (ref "U21") (pin "4") (pinfunction "7_4") (pintype "passive+no_connect"))
    )
    (net (code "103") (name "unconnected-(U21-Pad5)") (class "Default")
      (node (ref "U21") (pin "5") (pinfunction "5_5") (pintype "passive+no_connect"))
    )
    (net (code "104") (name "unconnected-(U22-6-Pad2)") (class "Default")
      (node (ref "U22") (pin "2") (pinfunction "6_2") (pintype "passive+no_connect"))
    )
    (net (code "105") (name "unconnected-(U22-7-Pad4)") (class "Default")
      (node (ref "U22") (pin "4") (pinfunction "7_4") (pintype "passive+no_connect"))
    )
    (net (code "106") (name "unconnected-(U22-Pad5)") (class "Default")
      (node (ref "U22") (pin "5") (pinfunction "5_5") (pintype "passive+no_connect"))
    )
    (net (code "107") (name "unconnected-(U31-ADDR-Pad4)") (class "Default")
      (node (ref "U31") (pin "4") (pinfunction "ADDR_4") (pintype "input+no_connect"))
    )
    (net (code "108") (name "unconnected-(U61-Pad5)") (class "Default")
      (node (ref "U61") (pin "5") (pinfunction "5_5") (pintype "passive+no_connect"))
    )
  )
)
